# clouds_v30.net
KiCad netlist of a schematic drawn in EAGLE
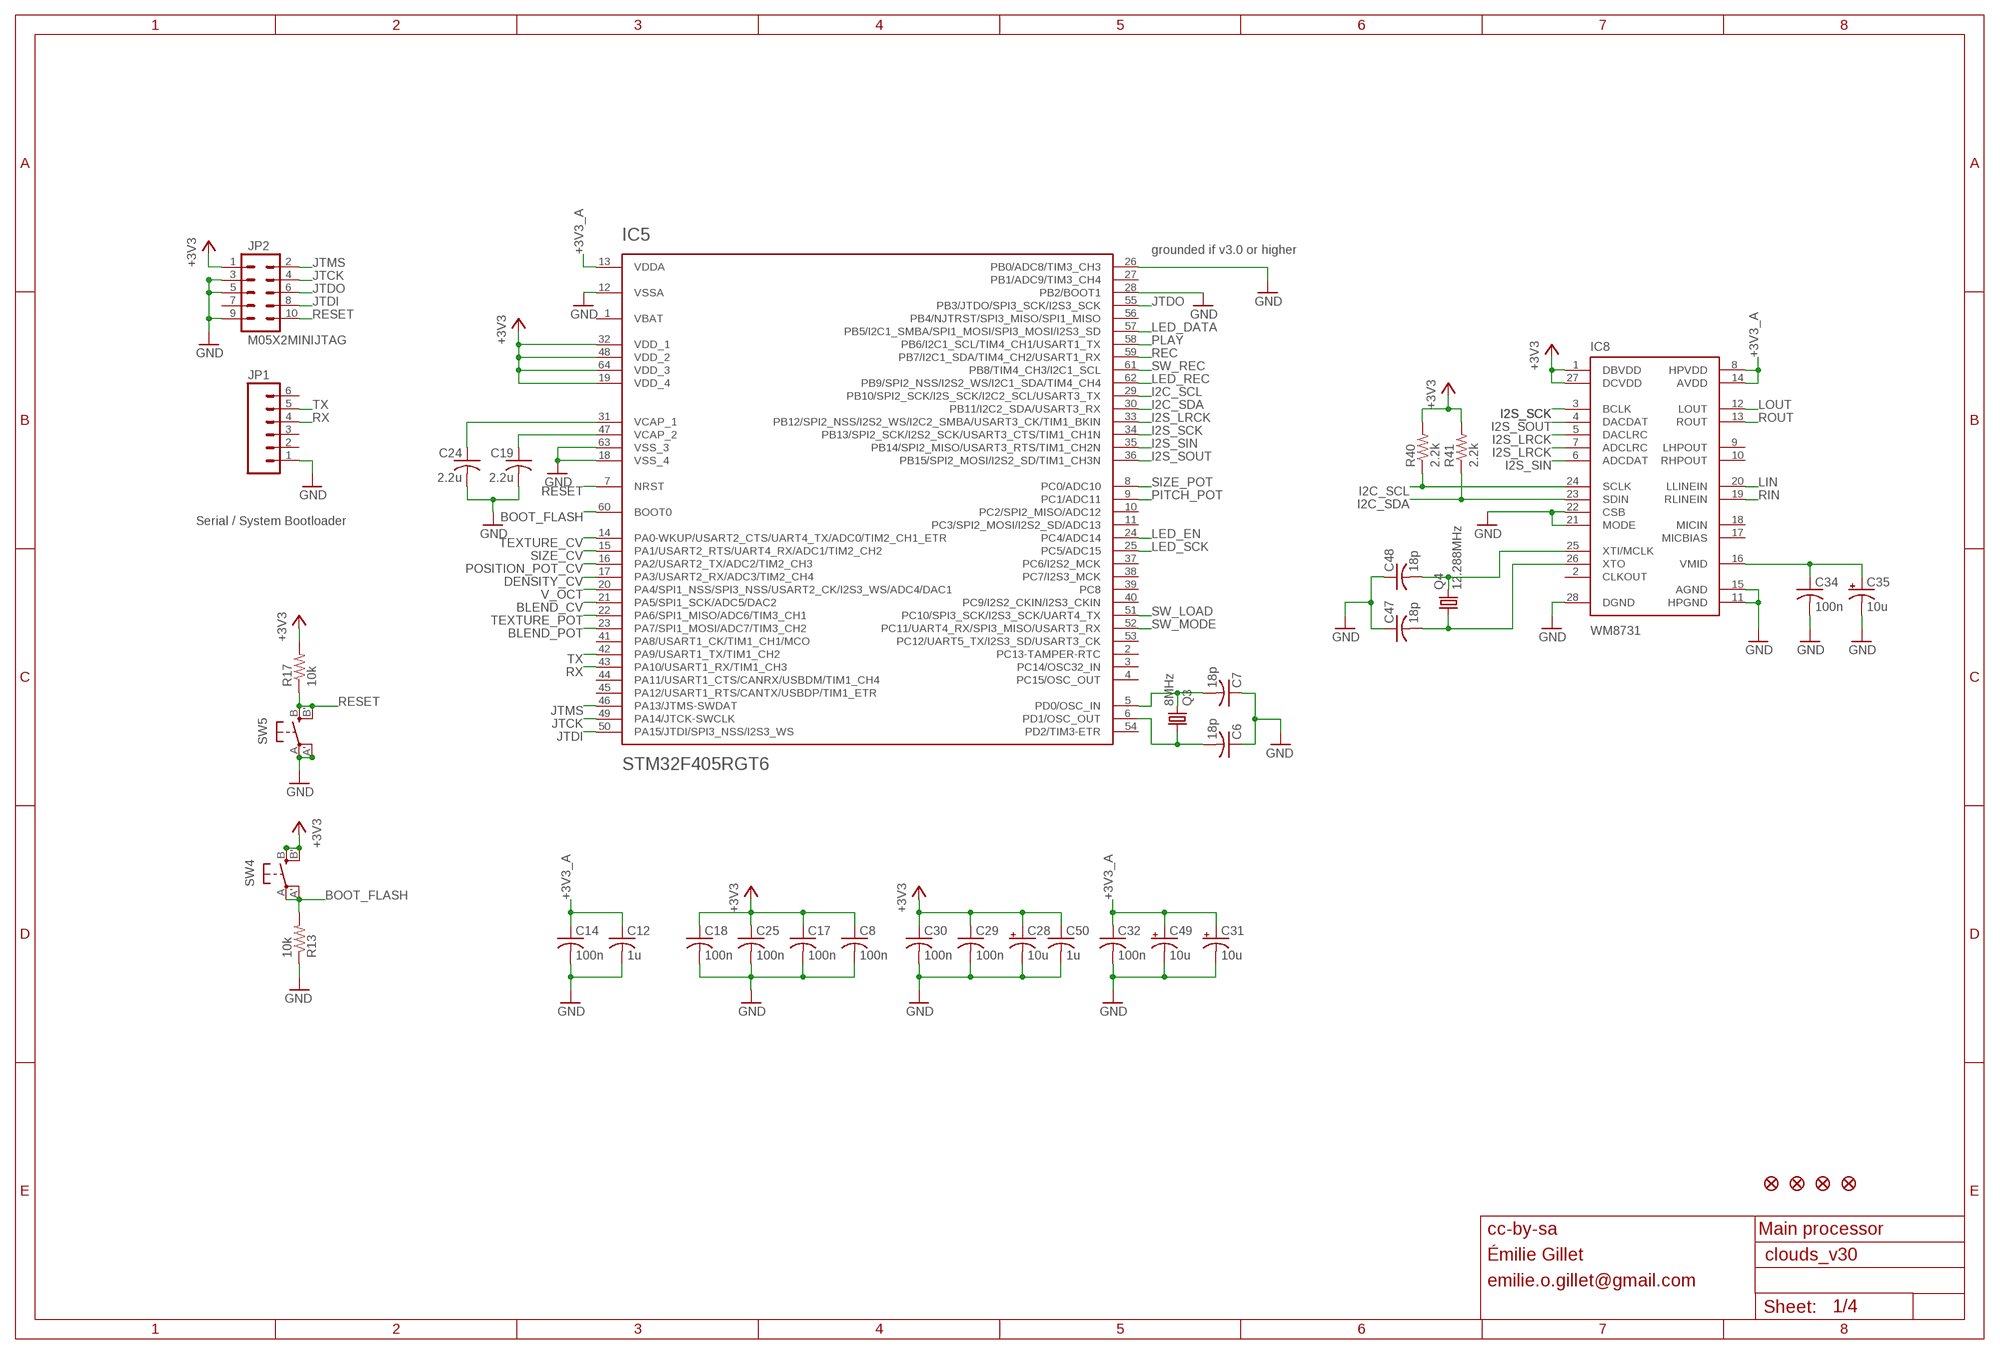
[diagram p0: schematic, sheet 1]
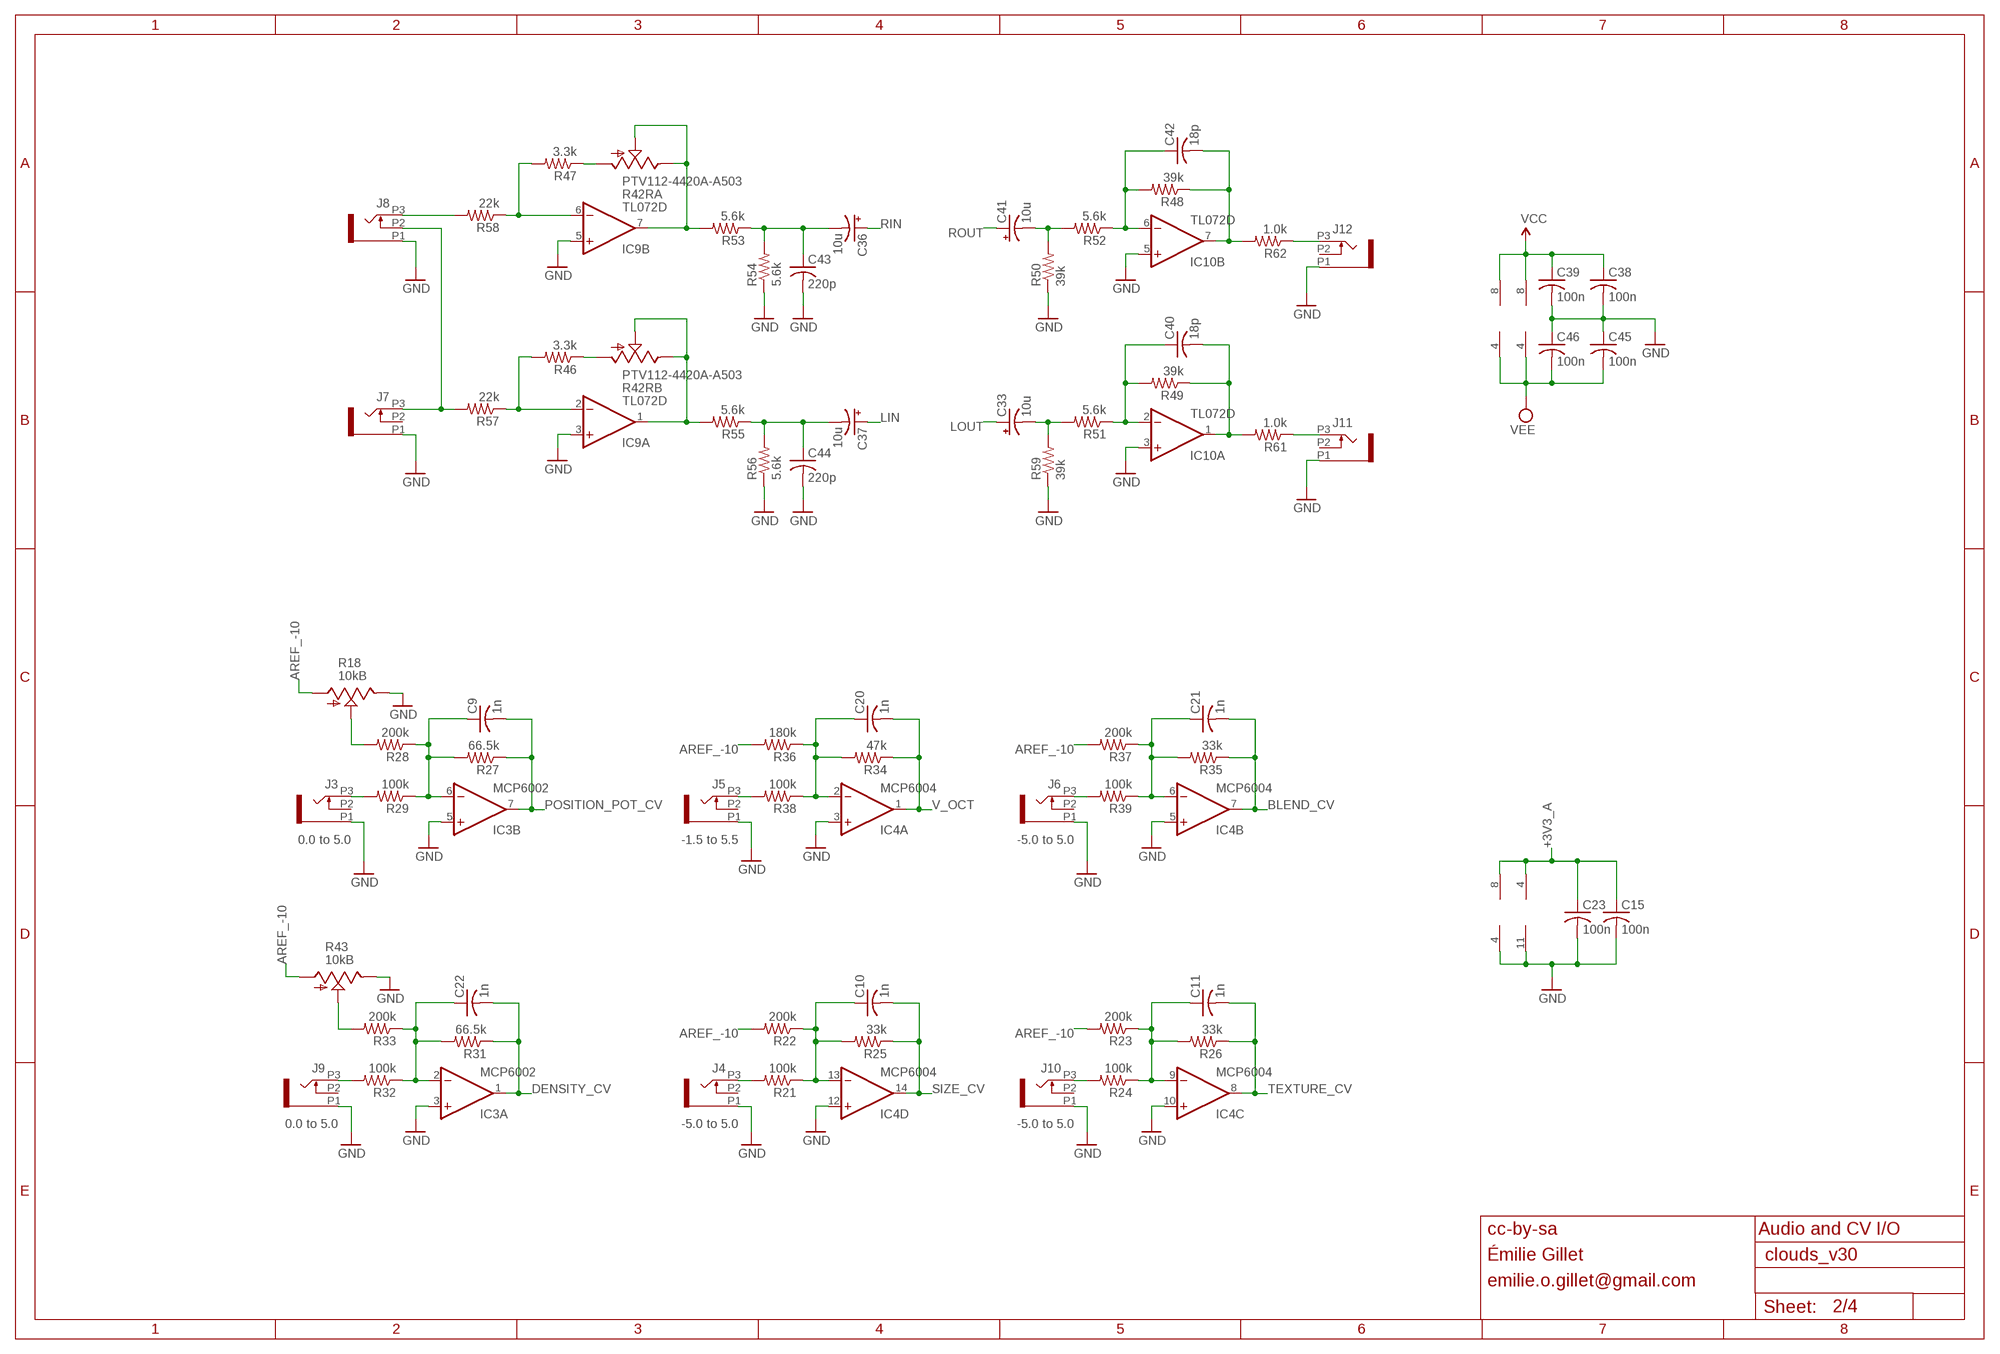
[diagram p1: schematic, sheet 2]
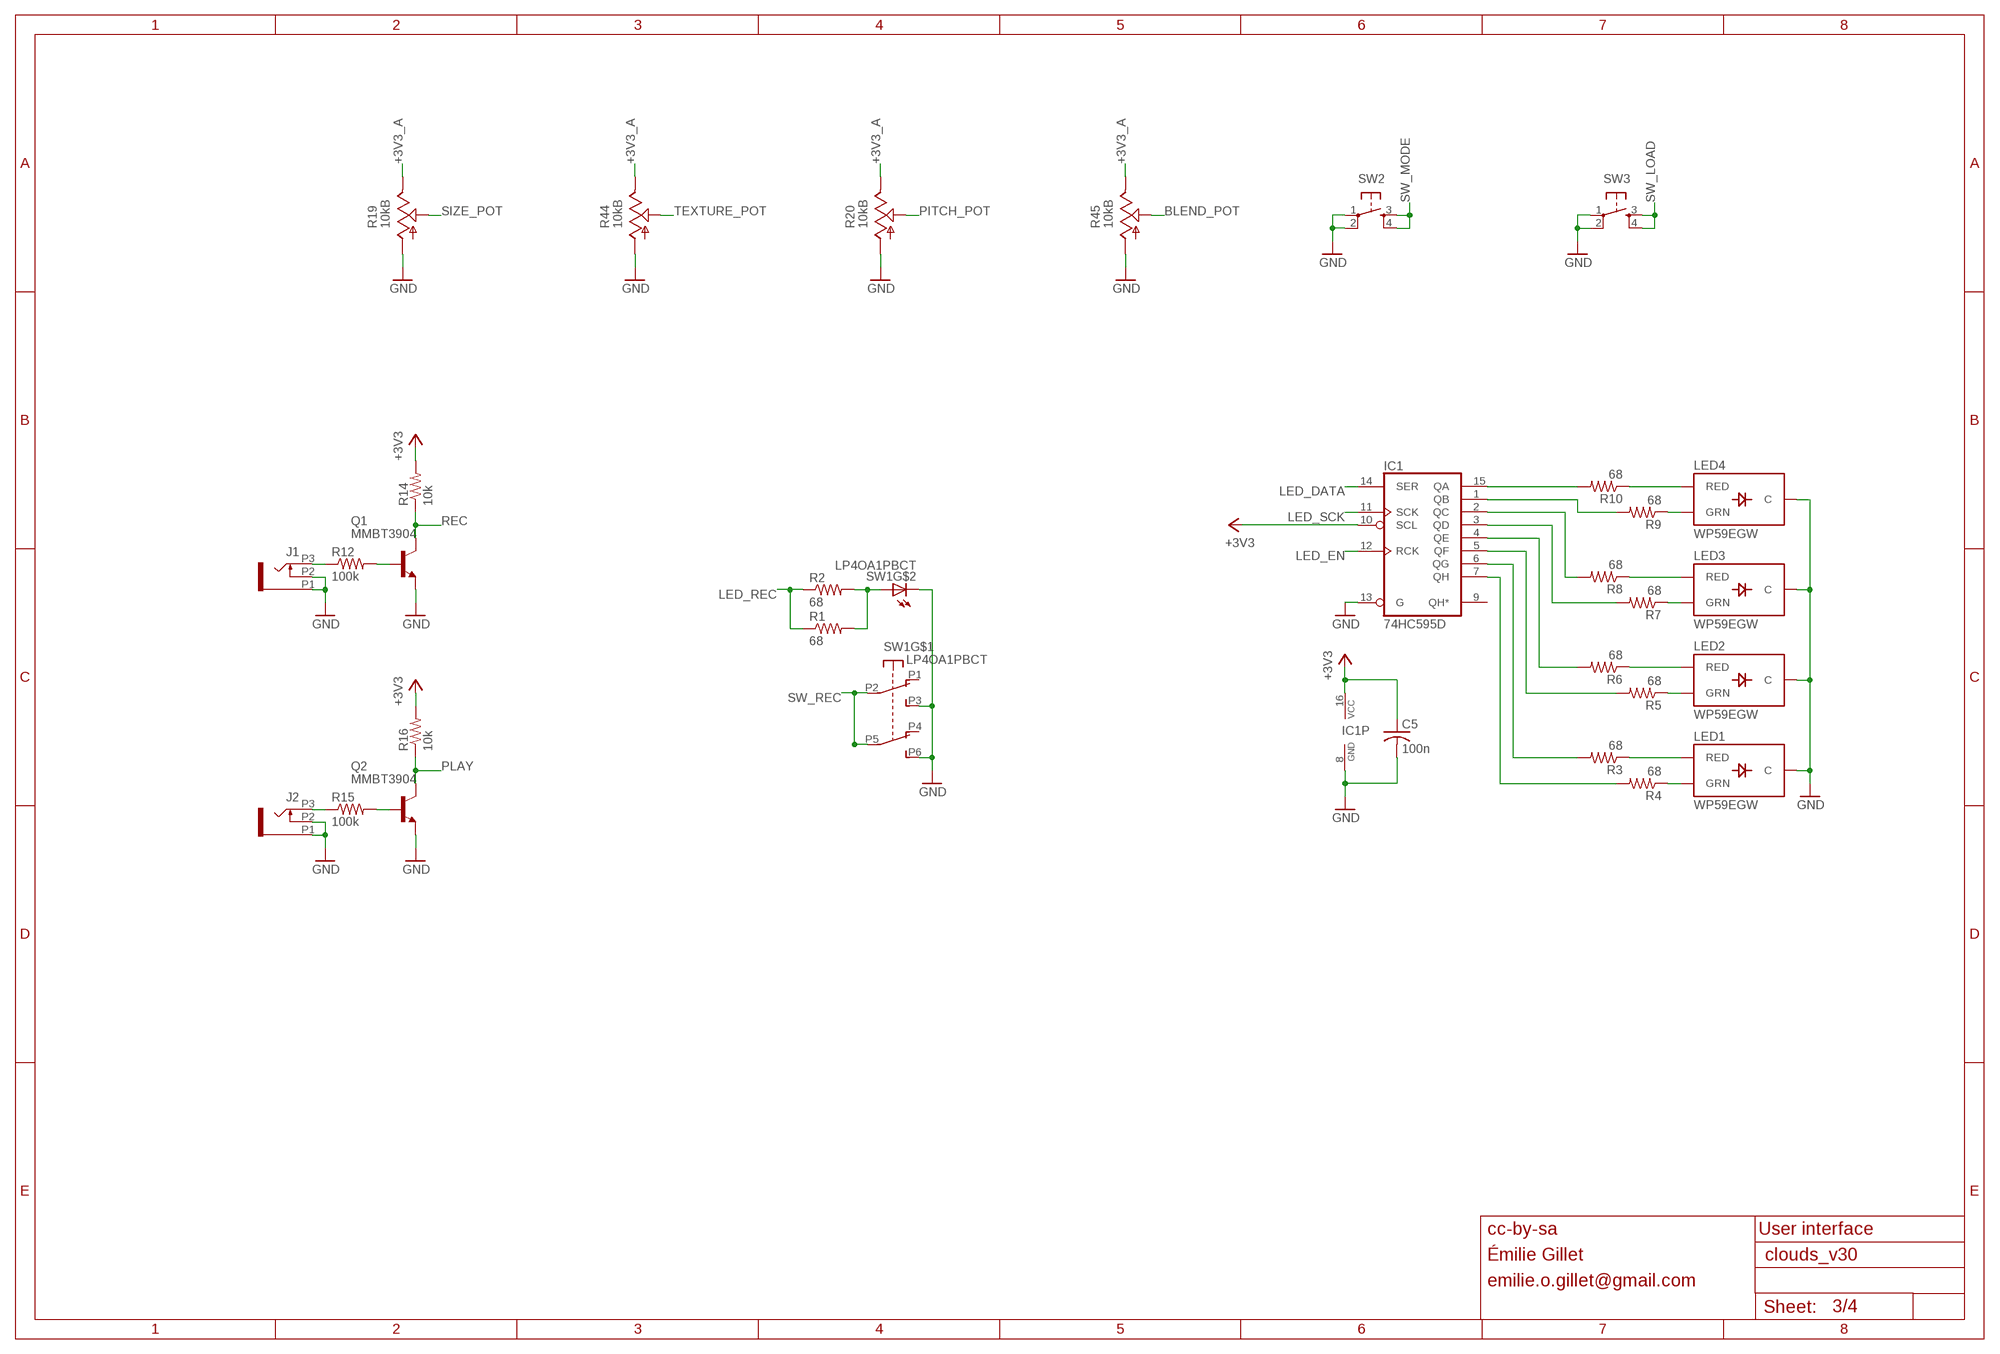
[diagram p2: schematic, sheet 3]
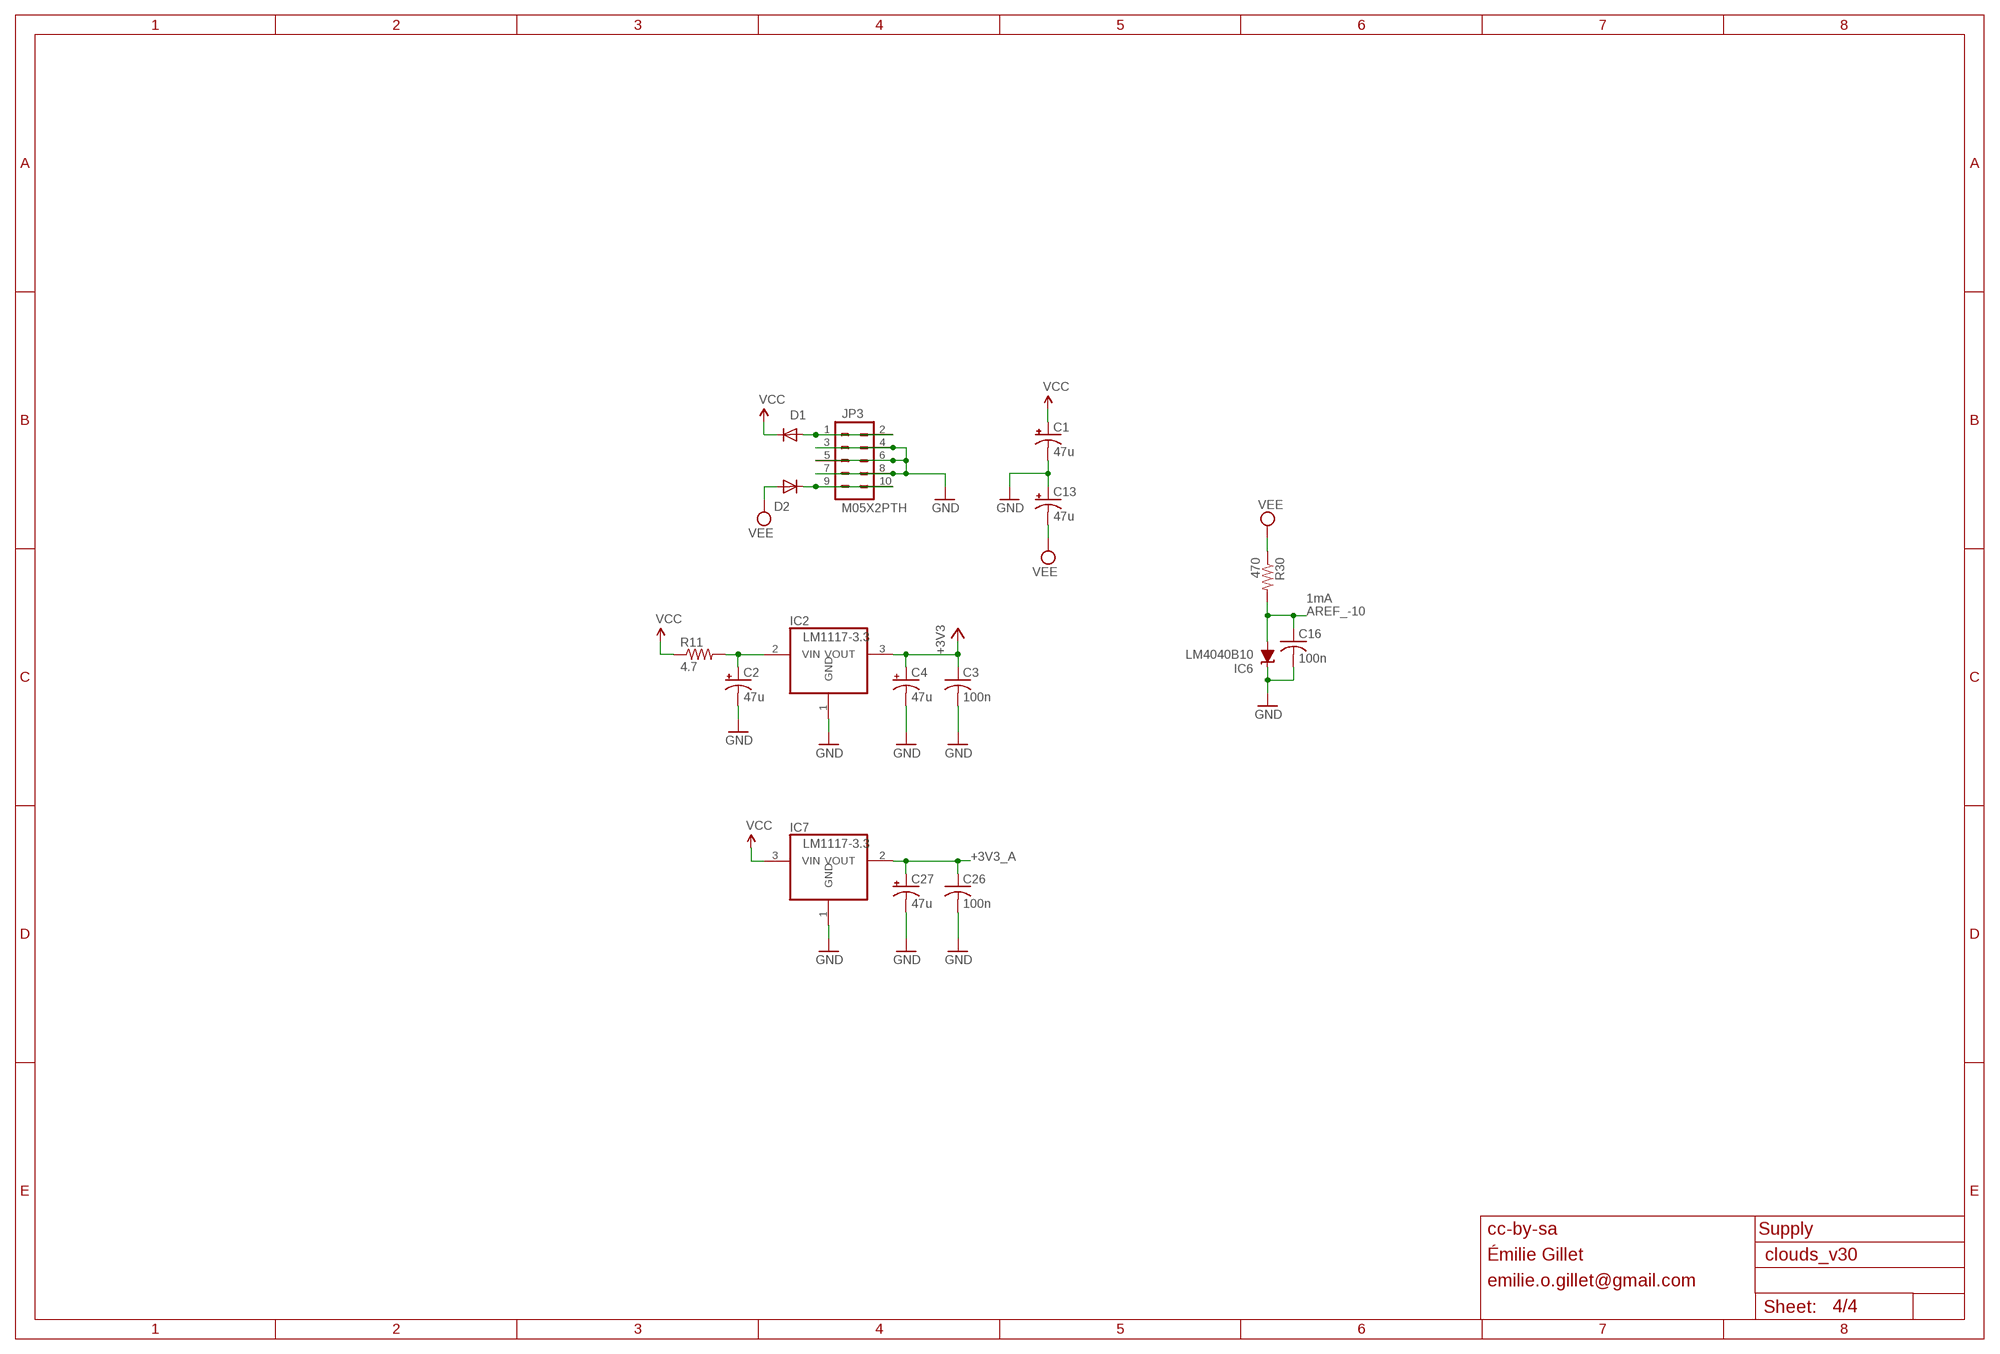
[diagram p3: schematic, sheet 4]

(export (version "E")
  (design (tool "Eeschema 10.0.6"))
  (components
    (comp (ref "C9")
      (value "1n")
      (footprint "eagle-import:C0603")
      (libsource (lib "eagle-import") (part "C-USC0603"))
    )
    (comp (ref "C10")
      (value "1n")
      (footprint "eagle-import:C0603")
      (libsource (lib "eagle-import") (part "C-USC0603"))
    )
    (comp (ref "C11")
      (value "1n")
      (footprint "eagle-import:C0603")
      (libsource (lib "eagle-import") (part "C-USC0603"))
    )
    (comp (ref "C15")
      (value "100n")
      (footprint "eagle-import:C0603")
      (libsource (lib "eagle-import") (part "C-USC0603"))
    )
    (comp (ref "C20")
      (value "1n")
      (footprint "eagle-import:C0603")
      (libsource (lib "eagle-import") (part "C-USC0603"))
    )
    (comp (ref "C21")
      (value "1n")
      (footprint "eagle-import:C0603")
      (libsource (lib "eagle-import") (part "C-USC0603"))
    )
    (comp (ref "C22")
      (value "1n")
      (footprint "eagle-import:C0603")
      (libsource (lib "eagle-import") (part "C-USC0603"))
    )
    (comp (ref "C23")
      (value "100n")
      (footprint "eagle-import:C0603")
      (libsource (lib "eagle-import") (part "C-USC0603"))
    )
    (comp (ref "C33")
      (value "10u")
      (footprint "eagle-import:PANASONIC_B")
      (libsource (lib "eagle-import") (part "CPOL-USB"))
    )
    (comp (ref "C36")
      (value "10u")
      (footprint "eagle-import:PANASONIC_B")
      (libsource (lib "eagle-import") (part "CPOL-USB"))
    )
    (comp (ref "C37")
      (value "10u")
      (footprint "eagle-import:PANASONIC_B")
      (libsource (lib "eagle-import") (part "CPOL-USB"))
    )
    (comp (ref "C38")
      (value "100n")
      (footprint "eagle-import:C0603")
      (libsource (lib "eagle-import") (part "C-USC0603"))
    )
    (comp (ref "C39")
      (value "100n")
      (footprint "eagle-import:C0603")
      (libsource (lib "eagle-import") (part "C-USC0603"))
    )
    (comp (ref "C40")
      (value "18p")
      (footprint "eagle-import:C0603")
      (libsource (lib "eagle-import") (part "C-USC0603"))
    )
    (comp (ref "C41")
      (value "10u")
      (footprint "eagle-import:PANASONIC_B")
      (libsource (lib "eagle-import") (part "CPOL-USB"))
    )
    (comp (ref "C42")
      (value "18p")
      (footprint "eagle-import:C0603")
      (libsource (lib "eagle-import") (part "C-USC0603"))
    )
    (comp (ref "C43")
      (value "220p")
      (footprint "eagle-import:C0603")
      (libsource (lib "eagle-import") (part "C-USC0603"))
    )
    (comp (ref "C44")
      (value "220p")
      (footprint "eagle-import:C0603")
      (libsource (lib "eagle-import") (part "C-USC0603"))
    )
    (comp (ref "C45")
      (value "100n")
      (footprint "eagle-import:C0603")
      (libsource (lib "eagle-import") (part "C-USC0603"))
    )
    (comp (ref "C46")
      (value "100n")
      (footprint "eagle-import:C0603")
      (libsource (lib "eagle-import") (part "C-USC0603"))
    )
    (comp (ref "IC3")
      (value "MCP6002")
      (footprint "eagle-import:SO08")
      (libsource (lib "eagle-import") (part "TL072D"))
    )
    (comp (ref "IC4")
      (value "MCP6004")
      (footprint "eagle-import:SO14")
      (libsource (lib "eagle-import") (part "TL074D"))
    )
    (comp (ref "IC9")
      (value "TL072D")
      (footprint "eagle-import:SO08")
      (libsource (lib "eagle-import") (part "og-linear_TL072D"))
    )
    (comp (ref "IC10")
      (value "TL072D")
      (footprint "eagle-import:SO08")
      (libsource (lib "eagle-import") (part "og-linear_TL072D"))
    )
    (comp (ref "J3")
      (value "PJ301_THONKICONN6")
      (footprint "eagle-import:WQP_PJ_301M6")
      (libsource (lib "eagle-import") (part "PJ301_THONKICONN6"))
    )
    (comp (ref "J4")
      (value "PJ301_THONKICONN6")
      (footprint "eagle-import:WQP_PJ_301M6")
      (libsource (lib "eagle-import") (part "PJ301_THONKICONN6"))
    )
    (comp (ref "J5")
      (value "PJ301_THONKICONN6")
      (footprint "eagle-import:WQP_PJ_301M6")
      (libsource (lib "eagle-import") (part "PJ301_THONKICONN6"))
    )
    (comp (ref "J6")
      (value "PJ301_THONKICONN6")
      (footprint "eagle-import:WQP_PJ_301M6")
      (libsource (lib "eagle-import") (part "PJ301_THONKICONN6"))
    )
    (comp (ref "J7")
      (value "PJ301_THONKICONN6")
      (footprint "eagle-import:WQP_PJ_301M6")
      (libsource (lib "eagle-import") (part "PJ301_THONKICONN6"))
    )
    (comp (ref "J8")
      (value "PJ301_THONKICONN6")
      (footprint "eagle-import:WQP_PJ_301M6")
      (libsource (lib "eagle-import") (part "PJ301_THONKICONN6"))
    )
    (comp (ref "J9")
      (value "PJ301_THONKICONN6")
      (footprint "eagle-import:WQP_PJ_301M6")
      (libsource (lib "eagle-import") (part "PJ301_THONKICONN6"))
    )
    (comp (ref "J10")
      (value "PJ301_THONKICONN6")
      (footprint "eagle-import:WQP_PJ_301M6")
      (libsource (lib "eagle-import") (part "PJ301_THONKICONN6"))
    )
    (comp (ref "J11")
      (value "PJ301_THONKICONN6")
      (footprint "eagle-import:WQP_PJ_301M6")
      (libsource (lib "eagle-import") (part "PJ301_THONKICONN6"))
    )
    (comp (ref "J12")
      (value "PJ301_THONKICONN6")
      (footprint "eagle-import:WQP_PJ_301M6")
      (libsource (lib "eagle-import") (part "PJ301_THONKICONN6"))
    )
    (comp (ref "R18")
      (value "10kB")
      (footprint "eagle-import:ALPS_POT_VERTICAL_PS")
      (libsource (lib "eagle-import") (part "POT_USVERTICAL_PS"))
    )
    (comp (ref "R21")
      (value "100k")
      (footprint "eagle-import:R0603")
      (libsource (lib "eagle-import") (part "R-US_R0603"))
    )
    (comp (ref "R22")
      (value "200k")
      (footprint "eagle-import:R0603")
      (libsource (lib "eagle-import") (part "R-US_R0603"))
    )
    (comp (ref "R23")
      (value "200k")
      (footprint "eagle-import:R0603")
      (libsource (lib "eagle-import") (part "R-US_R0603"))
    )
    (comp (ref "R24")
      (value "100k")
      (footprint "eagle-import:R0603")
      (libsource (lib "eagle-import") (part "R-US_R0603"))
    )
    (comp (ref "R25")
      (value "33k")
      (footprint "eagle-import:R0603")
      (libsource (lib "eagle-import") (part "R-US_R0603"))
    )
    (comp (ref "R26")
      (value "33k")
      (footprint "eagle-import:R0603")
      (libsource (lib "eagle-import") (part "R-US_R0603"))
    )
    (comp (ref "R27")
      (value "66.5k")
      (footprint "eagle-import:R0603")
      (libsource (lib "eagle-import") (part "R-US_R0603"))
    )
    (comp (ref "R28")
      (value "200k")
      (footprint "eagle-import:R0603")
      (libsource (lib "eagle-import") (part "R-US_R0603"))
    )
    (comp (ref "R29")
      (value "100k")
      (footprint "eagle-import:R0603")
      (libsource (lib "eagle-import") (part "R-US_R0603"))
    )
    (comp (ref "R31")
      (value "66.5k")
      (footprint "eagle-import:R0603")
      (libsource (lib "eagle-import") (part "R-US_R0603"))
    )
    (comp (ref "R32")
      (value "100k")
      (footprint "eagle-import:R0603")
      (libsource (lib "eagle-import") (part "R-US_R0603"))
    )
    (comp (ref "R33")
      (value "200k")
      (footprint "eagle-import:R0603")
      (libsource (lib "eagle-import") (part "R-US_R0603"))
    )
    (comp (ref "R34")
      (value "47k")
      (footprint "eagle-import:R0603")
      (libsource (lib "eagle-import") (part "R-US_R0603"))
    )
    (comp (ref "R35")
      (value "33k")
      (footprint "eagle-import:R0603")
      (libsource (lib "eagle-import") (part "R-US_R0603"))
    )
    (comp (ref "R36")
      (value "180k")
      (footprint "eagle-import:R0603")
      (libsource (lib "eagle-import") (part "R-US_R0603"))
    )
    (comp (ref "R37")
      (value "200k")
      (footprint "eagle-import:R0603")
      (libsource (lib "eagle-import") (part "R-US_R0603"))
    )
    (comp (ref "R38")
      (value "100k")
      (footprint "eagle-import:R0603")
      (libsource (lib "eagle-import") (part "R-US_R0603"))
    )
    (comp (ref "R39")
      (value "100k")
      (footprint "eagle-import:R0603")
      (libsource (lib "eagle-import") (part "R-US_R0603"))
    )
    (comp (ref "R42")
      (value "PTV112-4420A-A503")
      (footprint "eagle-import:BOURNS_PTV112")
      (libsource (lib "eagle-import") (part "POT_US_DUAL_GANG"))
    )
    (comp (ref "R43")
      (value "10kB")
      (footprint "eagle-import:ALPS_POT_VERTICAL_PS")
      (libsource (lib "eagle-import") (part "POT_USVERTICAL_PS"))
    )
    (comp (ref "R46")
      (value "3.3k")
      (footprint "eagle-import:R0603")
      (libsource (lib "eagle-import") (part "R-US_R0603"))
    )
    (comp (ref "R47")
      (value "3.3k")
      (footprint "eagle-import:R0603")
      (libsource (lib "eagle-import") (part "R-US_R0603"))
    )
    (comp (ref "R48")
      (value "39k")
      (footprint "eagle-import:R0603")
      (libsource (lib "eagle-import") (part "R-US_R0603"))
    )
    (comp (ref "R49")
      (value "39k")
      (footprint "eagle-import:R0603")
      (libsource (lib "eagle-import") (part "R-US_R0603"))
    )
    (comp (ref "R50")
      (value "39k")
      (footprint "eagle-import:R0603")
      (libsource (lib "eagle-import") (part "R-US_R0603"))
    )
    (comp (ref "R51")
      (value "5.6k")
      (footprint "eagle-import:R0603")
      (libsource (lib "eagle-import") (part "R-US_R0603"))
    )
    (comp (ref "R52")
      (value "5.6k")
      (footprint "eagle-import:R0603")
      (libsource (lib "eagle-import") (part "R-US_R0603"))
    )
    (comp (ref "R53")
      (value "5.6k")
      (footprint "eagle-import:R0603")
      (libsource (lib "eagle-import") (part "R-US_R0603"))
    )
    (comp (ref "R54")
      (value "5.6k")
      (footprint "eagle-import:R0603")
      (libsource (lib "eagle-import") (part "R-US_R0603"))
    )
    (comp (ref "R55")
      (value "5.6k")
      (footprint "eagle-import:R0603")
      (libsource (lib "eagle-import") (part "R-US_R0603"))
    )
    (comp (ref "R56")
      (value "5.6k")
      (footprint "eagle-import:R0603")
      (libsource (lib "eagle-import") (part "R-US_R0603"))
    )
    (comp (ref "R57")
      (value "22k")
      (footprint "eagle-import:R0603")
      (libsource (lib "eagle-import") (part "R-US_R0603"))
    )
    (comp (ref "R58")
      (value "22k")
      (footprint "eagle-import:R0603")
      (libsource (lib "eagle-import") (part "R-US_R0603"))
    )
    (comp (ref "R59")
      (value "39k")
      (footprint "eagle-import:R0603")
      (libsource (lib "eagle-import") (part "R-US_R0603"))
    )
    (comp (ref "R61")
      (value "1.0k")
      (footprint "eagle-import:R0603")
      (libsource (lib "eagle-import") (part "R-US_R0603"))
    )
    (comp (ref "R62")
      (value "1.0k")
      (footprint "eagle-import:R0603")
      (libsource (lib "eagle-import") (part "R-US_R0603"))
    )
    (comp (ref "C5")
      (value "100n")
      (footprint "eagle-import:C0603")
      (libsource (lib "eagle-import") (part "C-USC0603"))
    )
    (comp (ref "IC1")
      (value "74HC595D")
      (footprint "eagle-import:SO16")
      (libsource (lib "eagle-import") (part "74595DHC"))
    )
    (comp (ref "J1")
      (value "PJ301_THONKICONN6")
      (footprint "eagle-import:WQP_PJ_301M6")
      (libsource (lib "eagle-import") (part "PJ301_THONKICONN6"))
    )
    (comp (ref "J2")
      (value "PJ301_THONKICONN6")
      (footprint "eagle-import:WQP_PJ_301M6")
      (libsource (lib "eagle-import") (part "PJ301_THONKICONN6"))
    )
    (comp (ref "LED1")
      (value "WP59EGW")
      (footprint "eagle-import:LED-BICOLOR-THROUGHHOLE-5MM")
      (libsource (lib "eagle-import") (part "LED-BICOLOR-THROUGHHOLE5MM"))
    )
    (comp (ref "LED2")
      (value "WP59EGW")
      (footprint "eagle-import:LED-BICOLOR-THROUGHHOLE-5MM")
      (libsource (lib "eagle-import") (part "LED-BICOLOR-THROUGHHOLE5MM"))
    )
    (comp (ref "LED3")
      (value "WP59EGW")
      (footprint "eagle-import:LED-BICOLOR-THROUGHHOLE-5MM")
      (libsource (lib "eagle-import") (part "LED-BICOLOR-THROUGHHOLE5MM"))
    )
    (comp (ref "LED4")
      (value "WP59EGW")
      (footprint "eagle-import:LED-BICOLOR-THROUGHHOLE-5MM")
      (libsource (lib "eagle-import") (part "LED-BICOLOR-THROUGHHOLE5MM"))
    )
    (comp (ref "Q1")
      (value "MMBT3904")
      (footprint "eagle-import:SOT23-BEC")
      (libsource (lib "eagle-import") (part "-NPN-SOT23-BECMMBT3904LT1"))
    )
    (comp (ref "Q2")
      (value "MMBT3904")
      (footprint "eagle-import:SOT23-BEC")
      (libsource (lib "eagle-import") (part "-NPN-SOT23-BECMMBT3904LT1"))
    )
    (comp (ref "R1")
      (value "68")
      (footprint "eagle-import:R0603")
      (libsource (lib "eagle-import") (part "R-US_R0603"))
    )
    (comp (ref "R2")
      (value "68")
      (footprint "eagle-import:R0603")
      (libsource (lib "eagle-import") (part "R-US_R0603"))
    )
    (comp (ref "R3")
      (value "68")
      (footprint "eagle-import:R0603")
      (libsource (lib "eagle-import") (part "R-US_R0603"))
    )
    (comp (ref "R4")
      (value "68")
      (footprint "eagle-import:R0603")
      (libsource (lib "eagle-import") (part "R-US_R0603"))
    )
    (comp (ref "R5")
      (value "68")
      (footprint "eagle-import:R0603")
      (libsource (lib "eagle-import") (part "R-US_R0603"))
    )
    (comp (ref "R6")
      (value "68")
      (footprint "eagle-import:R0603")
      (libsource (lib "eagle-import") (part "R-US_R0603"))
    )
    (comp (ref "R7")
      (value "68")
      (footprint "eagle-import:R0603")
      (libsource (lib "eagle-import") (part "R-US_R0603"))
    )
    (comp (ref "R8")
      (value "68")
      (footprint "eagle-import:R0603")
      (libsource (lib "eagle-import") (part "R-US_R0603"))
    )
    (comp (ref "R9")
      (value "68")
      (footprint "eagle-import:R0603")
      (libsource (lib "eagle-import") (part "R-US_R0603"))
    )
    (comp (ref "R10")
      (value "68")
      (footprint "eagle-import:R0603")
      (libsource (lib "eagle-import") (part "R-US_R0603"))
    )
    (comp (ref "R12")
      (value "100k")
      (footprint "eagle-import:R0603")
      (libsource (lib "eagle-import") (part "R-US_R0603"))
    )
    (comp (ref "R14")
      (value "10k")
      (footprint "eagle-import:R0603")
      (libsource (lib "eagle-import") (part "R-US_R0603"))
    )
    (comp (ref "R15")
      (value "100k")
      (footprint "eagle-import:R0603")
      (libsource (lib "eagle-import") (part "R-US_R0603"))
    )
    (comp (ref "R16")
      (value "10k")
      (footprint "eagle-import:R0603")
      (libsource (lib "eagle-import") (part "R-US_R0603"))
    )
    (comp (ref "R19")
      (value "10kB")
      (footprint "eagle-import:ALPS_POT_VERTICAL_PS")
      (libsource (lib "eagle-import") (part "POT_USVERTICAL_PS"))
    )
    (comp (ref "R20")
      (value "10kB")
      (footprint "eagle-import:ALPS_POT_VERTICAL_PS")
      (libsource (lib "eagle-import") (part "POT_USVERTICAL_PS"))
    )
    (comp (ref "R44")
      (value "10kB")
      (footprint "eagle-import:ALPS_POT_VERTICAL_PS")
      (libsource (lib "eagle-import") (part "POT_USVERTICAL_PS"))
    )
    (comp (ref "R45")
      (value "10kB")
      (footprint "eagle-import:ALPS_POT_VERTICAL_PS")
      (libsource (lib "eagle-import") (part "POT_USVERTICAL_PS"))
    )
    (comp (ref "SW1")
      (value "LP4OA1PBCT")
      (footprint "eagle-import:LP4OA1PBCT")
      (libsource (lib "eagle-import") (part "LP4OA1PBCT"))
    )
    (comp (ref "SW2")
      (value "TAC_SWITCHPTH")
      (footprint "eagle-import:TACTILE-PTH")
      (libsource (lib "eagle-import") (part "TAC_SWITCHPTH"))
    )
    (comp (ref "SW3")
      (value "TAC_SWITCHPTH")
      (footprint "eagle-import:TACTILE-PTH")
      (libsource (lib "eagle-import") (part "TAC_SWITCHPTH"))
    )
    (comp (ref "C1")
      (value "47u")
      (footprint "eagle-import:PANASONIC_D")
      (libsource (lib "eagle-import") (part "CPOL-USD"))
    )
    (comp (ref "C2")
      (value "47u")
      (footprint "eagle-import:PANASONIC_D")
      (libsource (lib "eagle-import") (part "CPOL-USD"))
    )
    (comp (ref "C3")
      (value "100n")
      (footprint "eagle-import:C0603")
      (libsource (lib "eagle-import") (part "C-USC0603"))
    )
    (comp (ref "C4")
      (value "47u")
      (footprint "eagle-import:PANASONIC_D")
      (libsource (lib "eagle-import") (part "CPOL-USD"))
    )
    (comp (ref "C13")
      (value "47u")
      (footprint "eagle-import:PANASONIC_D")
      (libsource (lib "eagle-import") (part "CPOL-USD"))
    )
    (comp (ref "C16")
      (value "100n")
      (footprint "eagle-import:C0603")
      (libsource (lib "eagle-import") (part "C-USC0603"))
    )
    (comp (ref "C26")
      (value "100n")
      (footprint "eagle-import:C0603")
      (libsource (lib "eagle-import") (part "C-USC0603"))
    )
    (comp (ref "C27")
      (value "47u")
      (footprint "eagle-import:PANASONIC_D")
      (libsource (lib "eagle-import") (part "CPOL-USD"))
    )
    (comp (ref "D1")
      (value "1N5819HW")
      (footprint "eagle-import:SOD123")
      (libsource (lib "eagle-import") (part "DIODE-SOD123"))
    )
    (comp (ref "D2")
      (value "1N5819HW")
      (footprint "eagle-import:SOD123")
      (libsource (lib "eagle-import") (part "DIODE-SOD123"))
    )
    (comp (ref "IC2")
      (value "LM1117-3.3")
      (footprint "eagle-import:TO252")
      (libsource (lib "eagle-import") (part "REG1117T"))
    )
    (comp (ref "IC6")
      (value "LM4040B10")
      (footprint "eagle-import:DBZ_R-PDSO-G3")
      (libsource (lib "eagle-import") (part "LM4041DBZB12"))
    )
    (comp (ref "IC7")
      (value "LM1117-3.3")
      (footprint "eagle-import:SOT223")
      (libsource (lib "eagle-import") (part "REG1117"))
    )
    (comp (ref "JP3")
      (value "M05X2PTH")
      (footprint "eagle-import:AVR_ICSP")
      (libsource (lib "eagle-import") (part "M05X2PTH"))
    )
    (comp (ref "R11")
      (value "4.7")
      (footprint "eagle-import:R1206")
      (libsource (lib "eagle-import") (part "R-US_R1206"))
    )
    (comp (ref "R30")
      (value "470")
      (footprint "eagle-import:R0603")
      (libsource (lib "eagle-import") (part "R-US_R0603"))
    )
    (comp (ref "C6")
      (value "18p")
      (footprint "eagle-import:C0603")
      (libsource (lib "eagle-import") (part "C-USC0603"))
    )
    (comp (ref "C7")
      (value "18p")
      (footprint "eagle-import:C0603")
      (libsource (lib "eagle-import") (part "C-USC0603"))
    )
    (comp (ref "C8")
      (value "100n")
      (footprint "eagle-import:C0603")
      (libsource (lib "eagle-import") (part "C-USC0603"))
    )
    (comp (ref "C12")
      (value "1u")
      (footprint "eagle-import:C0603")
      (libsource (lib "eagle-import") (part "C-USC0603"))
    )
    (comp (ref "C14")
      (value "100n")
      (footprint "eagle-import:C0603")
      (libsource (lib "eagle-import") (part "C-USC0603"))
    )
    (comp (ref "C17")
      (value "100n")
      (footprint "eagle-import:C0603")
      (libsource (lib "eagle-import") (part "C-USC0603"))
    )
    (comp (ref "C18")
      (value "100n")
      (footprint "eagle-import:C0603")
      (libsource (lib "eagle-import") (part "C-USC0603"))
    )
    (comp (ref "C19")
      (value "2.2u")
      (footprint "eagle-import:C0805")
      (libsource (lib "eagle-import") (part "C-USC0805"))
    )
    (comp (ref "C24")
      (value "2.2u")
      (footprint "eagle-import:C0805")
      (libsource (lib "eagle-import") (part "C-USC0805"))
    )
    (comp (ref "C25")
      (value "100n")
      (footprint "eagle-import:C0603")
      (libsource (lib "eagle-import") (part "C-USC0603"))
    )
    (comp (ref "C28")
      (value "10u")
      (footprint "eagle-import:PANASONIC_A")
      (libsource (lib "eagle-import") (part "CPOL-USA"))
    )
    (comp (ref "C29")
      (value "100n")
      (footprint "eagle-import:C0603")
      (libsource (lib "eagle-import") (part "C-USC0603"))
    )
    (comp (ref "C30")
      (value "100n")
      (footprint "eagle-import:C0603")
      (libsource (lib "eagle-import") (part "C-USC0603"))
    )
    (comp (ref "C31")
      (value "10u")
      (footprint "eagle-import:PANASONIC_B")
      (libsource (lib "eagle-import") (part "CPOL-USB"))
    )
    (comp (ref "C32")
      (value "100n")
      (footprint "eagle-import:C0603")
      (libsource (lib "eagle-import") (part "C-USC0603"))
    )
    (comp (ref "C34")
      (value "100n")
      (footprint "eagle-import:C0603")
      (libsource (lib "eagle-import") (part "C-USC0603"))
    )
    (comp (ref "C35")
      (value "10u")
      (footprint "eagle-import:PANASONIC_B")
      (libsource (lib "eagle-import") (part "CPOL-USB"))
    )
    (comp (ref "C47")
      (value "18p")
      (footprint "eagle-import:C0603")
      (libsource (lib "eagle-import") (part "C-USC0603"))
    )
    (comp (ref "C48")
      (value "18p")
      (footprint "eagle-import:C0603")
      (libsource (lib "eagle-import") (part "C-USC0603"))
    )
    (comp (ref "C49")
      (value "10u")
      (footprint "eagle-import:PANASONIC_A")
      (libsource (lib "eagle-import") (part "CPOL-USA"))
    )
    (comp (ref "C50")
      (value "1u")
      (footprint "eagle-import:C0603")
      (libsource (lib "eagle-import") (part "C-USC0603"))
    )
    (comp (ref "F1")
      (value "FIDUCIAL1X2")
      (footprint "eagle-import:FIDUCIAL-1X2")
      (libsource (lib "eagle-import") (part "FIDUCIAL1X2"))
    )
    (comp (ref "F2")
      (value "FIDUCIAL1X2")
      (footprint "eagle-import:FIDUCIAL-1X2")
      (libsource (lib "eagle-import") (part "FIDUCIAL1X2"))
    )
    (comp (ref "F3")
      (value "FIDUCIAL1X2")
      (footprint "eagle-import:FIDUCIAL-1X2")
      (libsource (lib "eagle-import") (part "FIDUCIAL1X2"))
    )
    (comp (ref "F4")
      (value "FIDUCIAL1X2")
      (footprint "eagle-import:FIDUCIAL-1X2")
      (libsource (lib "eagle-import") (part "FIDUCIAL1X2"))
    )
    (comp (ref "IC5")
      (value "STM32F405RGT6")
      (footprint "eagle-import:TQFP-10X10-64")
      (libsource (lib "eagle-import") (part "STM32F20X"))
    )
    (comp (ref "IC8")
      (value "WM8731")
      (footprint "eagle-import:SSOP28")
      (libsource (lib "eagle-import") (part "WM8731"))
    )
    (comp (ref "JP1")
      (value "M06SIP")
      (footprint "eagle-import:1X06")
      (libsource (lib "eagle-import") (part "M06SIP"))
    )
    (comp (ref "JP2")
      (value "M05X2MINIJTAG")
      (footprint "eagle-import:2X5-1.27")
      (libsource (lib "eagle-import") (part "M05X2MINIJTAG"))
    )
    (comp (ref "Q3")
      (value "8MHz")
      (footprint "eagle-import:HC49UP")
      (libsource (lib "eagle-import") (part "CRYSTALHC49UP"))
    )
    (comp (ref "Q4")
      (value "12.288MHz")
      (footprint "eagle-import:HC49UP")
      (libsource (lib "eagle-import") (part "CRYSTALHC49UP"))
    )
    (comp (ref "R13")
      (value "10k")
      (footprint "eagle-import:R0603")
      (libsource (lib "eagle-import") (part "R-US_R0603"))
    )
    (comp (ref "R17")
      (value "10k")
      (footprint "eagle-import:R0603")
      (libsource (lib "eagle-import") (part "R-US_R0603"))
    )
    (comp (ref "R40")
      (value "2.2k")
      (footprint "eagle-import:R0603")
      (libsource (lib "eagle-import") (part "R-US_R0603"))
    )
    (comp (ref "R41")
      (value "2.2k")
      (footprint "eagle-import:R0603")
      (libsource (lib "eagle-import") (part "R-US_R0603"))
    )
    (comp (ref "SW4")
      (value "EVQQ2")
      (footprint "eagle-import:EVQ-Q2")
      (libsource (lib "eagle-import") (part "EVQQ2"))
    )
    (comp (ref "SW5")
      (value "EVQQ2")
      (footprint "eagle-import:EVQ-Q2")
      (libsource (lib "eagle-import") (part "EVQQ2"))
    )
  )
  (nets
    (net (code "1") (name "+3V3") (class "Default")
      (node (ref "C17") (pin "1") (pinfunction "1_1") (pintype "passive"))
      (node (ref "C18") (pin "1") (pinfunction "1_1") (pintype "passive"))
      (node (ref "C25") (pin "1") (pinfunction "1_1") (pintype "passive"))
      (node (ref "C28") (pin "+") (pinfunction "+_+") (pintype "passive"))
      (node (ref "C29") (pin "1") (pinfunction "1_1") (pintype "passive"))
      (node (ref "C3") (pin "1") (pinfunction "1_1") (pintype "passive"))
      (node (ref "C30") (pin "1") (pinfunction "1_1") (pintype "passive"))
      (node (ref "C4") (pin "+") (pinfunction "+_+") (pintype "passive"))
      (node (ref "C5") (pin "1") (pinfunction "1_1") (pintype "passive"))
      (node (ref "C50") (pin "1") (pinfunction "1_1") (pintype "passive"))
      (node (ref "C8") (pin "1") (pinfunction "1_1") (pintype "passive"))
      (node (ref "IC1") (pin "10") (pinfunction "SCL_10") (pintype "input"))
      (node (ref "IC1") (pin "16") (pinfunction "VCC_16") (pintype "power_in"))
      (node (ref "IC2") (pin "3") (pinfunction "VOUT_3") (pintype "output"))
      (node (ref "IC5") (pin "19") (pinfunction "VDD_4_19") (pintype "power_in"))
      (node (ref "IC5") (pin "32") (pinfunction "VDD_1_32") (pintype "power_in"))
      (node (ref "IC5") (pin "48") (pinfunction "VDD_2_48") (pintype "power_in"))
      (node (ref "IC5") (pin "64") (pinfunction "VDD_3_64") (pintype "power_in"))
      (node (ref "IC8") (pin "1") (pinfunction "DBVDD_1") (pintype "bidirectional"))
      (node (ref "IC8") (pin "27") (pinfunction "DCVDD_27") (pintype "bidirectional"))
      (node (ref "JP2") (pin "1") (pinfunction "1_1") (pintype "passive"))
      (node (ref "R14") (pin "2") (pinfunction "2_2") (pintype "passive"))
      (node (ref "R16") (pin "2") (pinfunction "2_2") (pintype "passive"))
      (node (ref "R17") (pin "2") (pinfunction "2_2") (pintype "passive"))
      (node (ref "R40") (pin "2") (pinfunction "2_2") (pintype "passive"))
      (node (ref "R41") (pin "2") (pinfunction "2_2") (pintype "passive"))
      (node (ref "SW4") (pin "B") (pinfunction "S_B") (pintype "passive"))
      (node (ref "SW4") (pin "B'") (pinfunction "S1_B'") (pintype "passive"))
    )
    (net (code "2") (name "+3V3_A") (class "Default")
      (node (ref "C12") (pin "1") (pinfunction "1_1") (pintype "passive"))
      (node (ref "C14") (pin "1") (pinfunction "1_1") (pintype "passive"))
      (node (ref "C15") (pin "1") (pinfunction "1_1") (pintype "passive"))
      (node (ref "C23") (pin "1") (pinfunction "1_1") (pintype "passive"))
      (node (ref "C26") (pin "1") (pinfunction "1_1") (pintype "passive"))
      (node (ref "C27") (pin "+") (pinfunction "+_+") (pintype "passive"))
      (node (ref "C31") (pin "+") (pinfunction "+_+") (pintype "passive"))
      (node (ref "C32") (pin "1") (pinfunction "1_1") (pintype "passive"))
      (node (ref "C49") (pin "+") (pinfunction "+_+") (pintype "passive"))
      (node (ref "IC3") (pin "8") (pinfunction "V+_8") (pintype "power_in"))
      (node (ref "IC4") (pin "4") (pinfunction "V+_4") (pintype "power_in"))
      (node (ref "IC5") (pin "13") (pinfunction "VDDA_13") (pintype "power_in"))
      (node (ref "IC7") (pin "2") (pinfunction "VOUT_2") (pintype "output"))
      (node (ref "IC8") (pin "14") (pinfunction "AVDD_14") (pintype "bidirectional"))
      (node (ref "IC8") (pin "8") (pinfunction "HPVDD_8") (pintype "bidirectional"))
      (node (ref "R19") (pin "P$1") (pinfunction "E_P$1") (pintype "passive"))
      (node (ref "R20") (pin "P$1") (pinfunction "E_P$1") (pintype "passive"))
      (node (ref "R44") (pin "P$1") (pinfunction "E_P$1") (pintype "passive"))
      (node (ref "R45") (pin "P$1") (pinfunction "E_P$1") (pintype "passive"))
    )
    (net (code "3") (name "AREF_-10") (class "Default")
      (node (ref "C16") (pin "1") (pinfunction "1_1") (pintype "passive"))
      (node (ref "IC6") (pin "2") (pinfunction "A_2") (pintype "passive"))
      (node (ref "R18") (pin "P$3") (pinfunction "A_P$3") (pintype "passive"))
      (node (ref "R22") (pin "2") (pinfunction "2_2") (pintype "passive"))
      (node (ref "R23") (pin "2") (pinfunction "2_2") (pintype "passive"))
      (node (ref "R30") (pin "2") (pinfunction "2_2") (pintype "passive"))
      (node (ref "R36") (pin "2") (pinfunction "2_2") (pintype "passive"))
      (node (ref "R37") (pin "2") (pinfunction "2_2") (pintype "passive"))
      (node (ref "R43") (pin "P$3") (pinfunction "A_P$3") (pintype "passive"))
    )
    (net (code "4") (name "BLEND_CV") (class "Default")
      (node (ref "C21") (pin "2") (pinfunction "2_2") (pintype "passive"))
      (node (ref "IC4") (pin "7") (pinfunction "OUT_7") (pintype "output"))
      (node (ref "IC5") (pin "21") (pinfunction "PA5/SPI1_SCK/ADC5/DAC2_21") (pintype "bidirectional"))
      (node (ref "R35") (pin "1") (pinfunction "1_1") (pintype "passive"))
    )
    (net (code "5") (name "BLEND_POT") (class "Default")
      (node (ref "IC5") (pin "23") (pinfunction "PA7/SPI1_MOSI/ADC7/TIM3_CH2_23") (pintype "bidirectional"))
      (node (ref "R45") (pin "P$2") (pinfunction "S_P$2") (pintype "passive"))
    )
    (net (code "6") (name "BOOT_FLASH") (class "Default")
      (node (ref "IC5") (pin "60") (pinfunction "BOOT0_60") (pintype "bidirectional"))
      (node (ref "R13") (pin "2") (pinfunction "2_2") (pintype "passive"))
      (node (ref "SW4") (pin "A") (pinfunction "P_A") (pintype "passive"))
      (node (ref "SW4") (pin "A'") (pinfunction "P1_A'") (pintype "passive"))
    )
    (net (code "7") (name "DENSITY_CV") (class "Default")
      (node (ref "C22") (pin "2") (pinfunction "2_2") (pintype "passive"))
      (node (ref "IC3") (pin "1") (pinfunction "OUT_1") (pintype "output"))
      (node (ref "IC5") (pin "17") (pinfunction "PA3/USART2_RX/ADC3/TIM2_CH4_17") (pintype "bidirectional"))
      (node (ref "R31") (pin "1") (pinfunction "1_1") (pintype "passive"))
    )
    (net (code "8") (name "GND") (class "Default")
      (node (ref "C1") (pin "-") (pinfunction "-_-") (pintype "passive"))
      (node (ref "C12") (pin "2") (pinfunction "2_2") (pintype "passive"))
      (node (ref "C13") (pin "+") (pinfunction "+_+") (pintype "passive"))
      (node (ref "C14") (pin "2") (pinfunction "2_2") (pintype "passive"))
      (node (ref "C15") (pin "2") (pinfunction "2_2") (pintype "passive"))
      (node (ref "C16") (pin "2") (pinfunction "2_2") (pintype "passive"))
      (node (ref "C17") (pin "2") (pinfunction "2_2") (pintype "passive"))
      (node (ref "C18") (pin "2") (pinfunction "2_2") (pintype "passive"))
      (node (ref "C19") (pin "2") (pinfunction "2_2") (pintype "passive"))
      (node (ref "C2") (pin "-") (pinfunction "-_-") (pintype "passive"))
      (node (ref "C23") (pin "2") (pinfunction "2_2") (pintype "passive"))
      (node (ref "C24") (pin "2") (pinfunction "2_2") (pintype "passive"))
      (node (ref "C25") (pin "2") (pinfunction "2_2") (pintype "passive"))
      (node (ref "C26") (pin "2") (pinfunction "2_2") (pintype "passive"))
      (node (ref "C27") (pin "-") (pinfunction "-_-") (pintype "passive"))
      (node (ref "C28") (pin "-") (pinfunction "-_-") (pintype "passive"))
      (node (ref "C29") (pin "2") (pinfunction "2_2") (pintype "passive"))
      (node (ref "C3") (pin "2") (pinfunction "2_2") (pintype "passive"))
      (node (ref "C30") (pin "2") (pinfunction "2_2") (pintype "passive"))
      (node (ref "C31") (pin "-") (pinfunction "-_-") (pintype "passive"))
      (node (ref "C32") (pin "2") (pinfunction "2_2") (pintype "passive"))
      (node (ref "C34") (pin "2") (pinfunction "2_2") (pintype "passive"))
      (node (ref "C35") (pin "-") (pinfunction "-_-") (pintype "passive"))
      (node (ref "C38") (pin "2") (pinfunction "2_2") (pintype "passive"))
      (node (ref "C39") (pin "2") (pinfunction "2_2") (pintype "passive"))
      (node (ref "C4") (pin "-") (pinfunction "-_-") (pintype "passive"))
      (node (ref "C43") (pin "2") (pinfunction "2_2") (pintype "passive"))
      (node (ref "C44") (pin "2") (pinfunction "2_2") (pintype "passive"))
      (node (ref "C45") (pin "1") (pinfunction "1_1") (pintype "passive"))
      (node (ref "C46") (pin "1") (pinfunction "1_1") (pintype "passive"))
      (node (ref "C47") (pin "1") (pinfunction "1_1") (pintype "passive"))
      (node (ref "C48") (pin "1") (pinfunction "1_1") (pintype "passive"))
      (node (ref "C49") (pin "-") (pinfunction "-_-") (pintype "passive"))
      (node (ref "C5") (pin "2") (pinfunction "2_2") (pintype "passive"))
      (node (ref "C50") (pin "2") (pinfunction "2_2") (pintype "passive"))
      (node (ref "C6") (pin "1") (pinfunction "1_1") (pintype "passive"))
      (node (ref "C7") (pin "1") (pinfunction "1_1") (pintype "passive"))
      (node (ref "C8") (pin "2") (pinfunction "2_2") (pintype "passive"))
      (node (ref "IC1") (pin "13") (pinfunction "G_13") (pintype "input"))
      (node (ref "IC1") (pin "8") (pinfunction "GND_8") (pintype "power_in"))
      (node (ref "IC10") (pin "3") (pinfunction "+IN_3") (pintype "input"))
      (node (ref "IC10") (pin "5") (pinfunction "+IN_5") (pintype "input"))
      (node (ref "IC2") (pin "1") (pinfunction "GND_1") (pintype "power_in"))
      (node (ref "IC3") (pin "3") (pinfunction "+IN_3") (pintype "input"))
      (node (ref "IC3") (pin "4") (pinfunction "V-_4") (pintype "power_in"))
      (node (ref "IC3") (pin "5") (pinfunction "+IN_5") (pintype "input"))
      (node (ref "IC4") (pin "10") (pinfunction "+IN_10") (pintype "input"))
      (node (ref "IC4") (pin "11") (pinfunction "V-_11") (pintype "power_in"))
      (node (ref "IC4") (pin "12") (pinfunction "+IN_12") (pintype "input"))
      (node (ref "IC4") (pin "3") (pinfunction "+IN_3") (pintype "input"))
      (node (ref "IC4") (pin "5") (pinfunction "+IN_5") (pintype "input"))
      (node (ref "IC5") (pin "12") (pinfunction "VSSA_12") (pintype "power_in"))
      (node (ref "IC5") (pin "18") (pinfunction "VSS_4_18") (pintype "power_in"))
      (node (ref "IC5") (pin "26") (pinfunction "PB0/ADC8/TIM3_CH3_26") (pintype "bidirectional"))
      (node (ref "IC5") (pin "28") (pinfunction "PB2/BOOT1_28") (pintype "bidirectional"))
      (node (ref "IC5") (pin "63") (pinfunction "VSS_3_63") (pintype "power_in"))
      (node (ref "IC6") (pin "1") (pinfunction "C_1") (pintype "passive"))
      (node (ref "IC7") (pin "1") (pinfunction "GND_1") (pintype "power_in"))
      (node (ref "IC8") (pin "11") (pinfunction "HPGND_11") (pintype "bidirectional"))
      (node (ref "IC8") (pin "15") (pinfunction "AGND_15") (pintype "bidirectional"))
      (node (ref "IC8") (pin "21") (pinfunction "MODE_21") (pintype "bidirectional"))
      (node (ref "IC8") (pin "22") (pinfunction "CSB_22") (pintype "bidirectional"))
      (node (ref "IC8") (pin "28") (pinfunction "DGND_28") (pintype "bidirectional"))
      (node (ref "IC9") (pin "3") (pinfunction "+IN_3") (pintype "input"))
      (node (ref "IC9") (pin "5") (pinfunction "+IN_5") (pintype "input"))
      (node (ref "J1") (pin "P1") (pinfunction "1_P1") (pintype "passive"))
      (node (ref "J1") (pin "P2") (pinfunction "2_P2") (pintype "passive"))
      (node (ref "J10") (pin "P1") (pinfunction "1_P1") (pintype "passive"))
      (node (ref "J11") (pin "P1") (pinfunction "1_P1") (pintype "passive"))
      (node (ref "J12") (pin "P1") (pinfunction "1_P1") (pintype "passive"))
      (node (ref "J2") (pin "P1") (pinfunction "1_P1") (pintype "passive"))
      (node (ref "J2") (pin "P2") (pinfunction "2_P2") (pintype "passive"))
      (node (ref "J3") (pin "P1") (pinfunction "1_P1") (pintype "passive"))
      (node (ref "J4") (pin "P1") (pinfunction "1_P1") (pintype "passive"))
      (node (ref "J5") (pin "P1") (pinfunction "1_P1") (pintype "passive"))
      (node (ref "J6") (pin "P1") (pinfunction "1_P1") (pintype "passive"))
      (node (ref "J7") (pin "P1") (pinfunction "1_P1") (pintype "passive"))
      (node (ref "J8") (pin "P1") (pinfunction "1_P1") (pintype "passive"))
      (node (ref "J9") (pin "P1") (pinfunction "1_P1") (pintype "passive"))
      (node (ref "JP1") (pin "1") (pinfunction "1_1") (pintype "passive"))
      (node (ref "JP2") (pin "3") (pinfunction "3_3") (pintype "passive"))
      (node (ref "JP2") (pin "5") (pinfunction "5_5") (pintype "passive"))
      (node (ref "JP2") (pin "9") (pinfunction "9_9") (pintype "passive"))
      (node (ref "JP3") (pin "3") (pinfunction "3_3") (pintype "passive"))
      (node (ref "JP3") (pin "4") (pinfunction "4_4") (pintype "passive"))
      (node (ref "JP3") (pin "5") (pinfunction "5_5") (pintype "passive"))
      (node (ref "JP3") (pin "6") (pinfunction "6_6") (pintype "passive"))
      (node (ref "JP3") (pin "7") (pinfunction "7_7") (pintype "passive"))
      (node (ref "JP3") (pin "8") (pinfunction "8_8") (pintype "passive"))
      (node (ref "LED1") (pin "2") (pinfunction "C_2") (pintype "bidirectional"))
      (node (ref "LED2") (pin "2") (pinfunction "C_2") (pintype "bidirectional"))
      (node (ref "LED3") (pin "2") (pinfunction "C_2") (pintype "bidirectional"))
      (node (ref "LED4") (pin "2") (pinfunction "C_2") (pintype "bidirectional"))
      (node (ref "Q1") (pin "E") (pinfunction "E_E") (pintype "passive"))
      (node (ref "Q2") (pin "E") (pinfunction "E_E") (pintype "passive"))
      (node (ref "R13") (pin "1") (pinfunction "1_1") (pintype "passive"))
      (node (ref "R18") (pin "P$1") (pinfunction "E_P$1") (pintype "passive"))
      (node (ref "R19") (pin "P$3") (pinfunction "A_P$3") (pintype "passive"))
      (node (ref "R20") (pin "P$3") (pinfunction "A_P$3") (pintype "passive"))
      (node (ref "R43") (pin "P$1") (pinfunction "E_P$1") (pintype "passive"))
      (node (ref "R44") (pin "P$3") (pinfunction "A_P$3") (pintype "passive"))
      (node (ref "R45") (pin "P$3") (pinfunction "A_P$3") (pintype "passive"))
      (node (ref "R50") (pin "1") (pinfunction "1_1") (pintype "passive"))
      (node (ref "R54") (pin "1") (pinfunction "1_1") (pintype "passive"))
      (node (ref "R56") (pin "1") (pinfunction "1_1") (pintype "passive"))
      (node (ref "R59") (pin "1") (pinfunction "1_1") (pintype "passive"))
      (node (ref "SW1") (pin "L2") (pinfunction "L2_L2") (pintype "passive"))
      (node (ref "SW1") (pin "P3") (pinfunction "A3_P3") (pintype "passive"))
      (node (ref "SW1") (pin "P6") (pinfunction "B3_P6") (pintype "passive"))
      (node (ref "SW2") (pin "1") (pinfunction "1_1") (pintype "passive"))
      (node (ref "SW2") (pin "2") (pinfunction "2_2") (pintype "passive"))
      (node (ref "SW3") (pin "1") (pinfunction "1_1") (pintype "passive"))
      (node (ref "SW3") (pin "2") (pinfunction "2_2") (pintype "passive"))
      (node (ref "SW5") (pin "A") (pinfunction "P_A") (pintype "passive"))
      (node (ref "SW5") (pin "A'") (pinfunction "P1_A'") (pintype "passive"))
    )
    (net (code "9") (name "I2C_SCL") (class "Default")
      (node (ref "IC5") (pin "29") (pinfunction "PB10/SPI2_SCK/I2S_SCK/I2C2_SCL/USART3_TX_29") (pintype "bidirectional"))
      (node (ref "IC8") (pin "24") (pinfunction "SCLK_24") (pintype "bidirectional"))
      (node (ref "R40") (pin "1") (pinfunction "1_1") (pintype "passive"))
    )
    (net (code "10") (name "I2C_SDA") (class "Default")
      (node (ref "IC5") (pin "30") (pinfunction "PB11/I2C2_SDA/USART3_RX_30") (pintype "bidirectional"))
      (node (ref "IC8") (pin "23") (pinfunction "SDIN_23") (pintype "bidirectional"))
      (node (ref "R41") (pin "1") (pinfunction "1_1") (pintype "passive"))
    )
    (net (code "11") (name "I2S_LRCK") (class "Default")
      (node (ref "IC5") (pin "33") (pinfunction "PB12/SPI2_NSS/I2S2_WS/I2C2_SMBA/USART3_CK/TIM1_BKIN_33") (pintype "bidirectional"))
      (node (ref "IC8") (pin "5") (pinfunction "DACLRC_5") (pintype "bidirectional"))
      (node (ref "IC8") (pin "7") (pinfunction "ADCLRC_7") (pintype "bidirectional"))
    )
    (net (code "12") (name "I2S_SCK") (class "Default")
      (node (ref "IC5") (pin "34") (pinfunction "PB13/SPI2_SCK/I2S2_SCK/USART3_CTS/TIM1_CH1N_34") (pintype "bidirectional"))
      (node (ref "IC8") (pin "3") (pinfunction "BCLK_3") (pintype "bidirectional"))
    )
    (net (code "13") (name "I2S_SIN") (class "Default")
      (node (ref "IC5") (pin "35") (pinfunction "PB14/SPI2_MISO/USART3_RTS/TIM1_CH2N_35") (pintype "bidirectional"))
      (node (ref "IC8") (pin "6") (pinfunction "ADCDAT_6") (pintype "bidirectional"))
    )
    (net (code "14") (name "I2S_SOUT") (class "Default")
      (node (ref "IC5") (pin "36") (pinfunction "PB15/SPI2_MOSI/I2S2_SD/TIM1_CH3N_36") (pintype "bidirectional"))
      (node (ref "IC8") (pin "4") (pinfunction "DACDAT_4") (pintype "bidirectional"))
    )
    (net (code "15") (name "JTCK") (class "Default")
      (node (ref "IC5") (pin "49") (pinfunction "PA14/JTCK-SWCLK_49") (pintype "bidirectional"))
      (node (ref "JP2") (pin "4") (pinfunction "4_4") (pintype "passive"))
    )
    (net (code "16") (name "JTDI") (class "Default")
      (node (ref "IC5") (pin "50") (pinfunction "PA15/JTDI/SPI3_NSS/I2S3_WS_50") (pintype "bidirectional"))
      (node (ref "JP2") (pin "8") (pinfunction "8_8") (pintype "passive"))
    )
    (net (code "17") (name "JTDO") (class "Default")
      (node (ref "IC5") (pin "55") (pinfunction "PB3/JTDO/SPI3_SCK/I2S3_SCK_55") (pintype "bidirectional"))
      (node (ref "JP2") (pin "6") (pinfunction "6_6") (pintype "passive"))
    )
    (net (code "18") (name "JTMS") (class "Default")
      (node (ref "IC5") (pin "46") (pinfunction "PA13/JTMS-SWDAT_46") (pintype "bidirectional"))
      (node (ref "JP2") (pin "2") (pinfunction "2_2") (pintype "passive"))
    )
    (net (code "19") (name "LED_DATA") (class "Default")
      (node (ref "IC1") (pin "14") (pinfunction "SER_14") (pintype "input"))
      (node (ref "IC5") (pin "57") (pinfunction "PB5/I2C1_SMBA/SPI1_MOSI/SPI3_MOSI/I2S3_SD_57") (pintype "bidirectional"))
    )
    (net (code "20") (name "LED_EN") (class "Default")
      (node (ref "IC1") (pin "12") (pinfunction "RCK_12") (pintype "input"))
      (node (ref "IC5") (pin "24") (pinfunction "PC4/ADC14_24") (pintype "bidirectional"))
    )
    (net (code "21") (name "LED_REC") (class "Default")
      (node (ref "IC5") (pin "62") (pinfunction "PB9/SPI2_NSS/I2S2_WS/I2C1_SDA/TIM4_CH4_62") (pintype "bidirectional"))
      (node (ref "R1") (pin "1") (pinfunction "1_1") (pintype "passive"))
      (node (ref "R2") (pin "1") (pinfunction "1_1") (pintype "passive"))
    )
    (net (code "22") (name "LED_SCK") (class "Default")
      (node (ref "IC1") (pin "11") (pinfunction "SCK_11") (pintype "input"))
      (node (ref "IC5") (pin "25") (pinfunction "PC5/ADC15_25") (pintype "bidirectional"))
    )
    (net (code "23") (name "LIN") (class "Default")
      (node (ref "C37") (pin "+") (pinfunction "+_+") (pintype "passive"))
      (node (ref "IC8") (pin "20") (pinfunction "LLINEIN_20") (pintype "bidirectional"))
    )
    (net (code "24") (name "LOUT") (class "Default")
      (node (ref "C33") (pin "+") (pinfunction "+_+") (pintype "passive"))
      (node (ref "IC8") (pin "12") (pinfunction "LOUT_12") (pintype "bidirectional"))
    )
    (net (code "25") (name "Net-(C33-Pad-)") (class "Default")
      (node (ref "C33") (pin "-") (pinfunction "-_-") (pintype "passive"))
      (node (ref "R51") (pin "2") (pinfunction "2_2") (pintype "passive"))
      (node (ref "R59") (pin "2") (pinfunction "2_2") (pintype "passive"))
    )
    (net (code "26") (name "Net-(C36-Pad-)") (class "Default")
      (node (ref "C36") (pin "-") (pinfunction "-_-") (pintype "passive"))
      (node (ref "C43") (pin "1") (pinfunction "1_1") (pintype "passive"))
      (node (ref "R53") (pin "1") (pinfunction "1_1") (pintype "passive"))
      (node (ref "R54") (pin "2") (pinfunction "2_2") (pintype "passive"))
    )
    (net (code "27") (name "Net-(C37-Pad-)") (class "Default")
      (node (ref "C37") (pin "-") (pinfunction "-_-") (pintype "passive"))
      (node (ref "C44") (pin "1") (pinfunction "1_1") (pintype "passive"))
      (node (ref "R55") (pin "1") (pinfunction "1_1") (pintype "passive"))
      (node (ref "R56") (pin "2") (pinfunction "2_2") (pintype "passive"))
    )
    (net (code "28") (name "Net-(C41-Pad-)") (class "Default")
      (node (ref "C41") (pin "-") (pinfunction "-_-") (pintype "passive"))
      (node (ref "R50") (pin "2") (pinfunction "2_2") (pintype "passive"))
      (node (ref "R52") (pin "2") (pinfunction "2_2") (pintype "passive"))
    )
    (net (code "29") (name "Net-(D1-PadA)") (class "Default")
      (node (ref "D1") (pin "A") (pinfunction "A_A") (pintype "passive"))
      (node (ref "JP3") (pin "1") (pinfunction "1_1") (pintype "passive"))
      (node (ref "JP3") (pin "2") (pinfunction "2_2") (pintype "passive"))
    )
    (net (code "30") (name "Net-(D2-PadC)") (class "Default")
      (node (ref "D2") (pin "C") (pinfunction "C_C") (pintype "passive"))
      (node (ref "JP3") (pin "10") (pinfunction "10_10") (pintype "passive"))
      (node (ref "JP3") (pin "9") (pinfunction "9_9") (pintype "passive"))
    )
    (net (code "31") (name "Net-(IC1A-QA)") (class "Default")
      (node (ref "IC1") (pin "15") (pinfunction "QA_15") (pintype "tri_state"))
      (node (ref "R10") (pin "2") (pinfunction "2_2") (pintype "passive"))
    )
    (net (code "32") (name "Net-(IC1A-QB)") (class "Default")
      (node (ref "IC1") (pin "1") (pinfunction "QB_1") (pintype "tri_state"))
      (node (ref "R9") (pin "2") (pinfunction "2_2") (pintype "passive"))
    )
    (net (code "33") (name "Net-(IC1A-QC)") (class "Default")
      (node (ref "IC1") (pin "2") (pinfunction "QC_2") (pintype "tri_state"))
      (node (ref "R8") (pin "2") (pinfunction "2_2") (pintype "passive"))
    )
    (net (code "34") (name "Net-(IC1A-QD)") (class "Default")
      (node (ref "IC1") (pin "3") (pinfunction "QD_3") (pintype "tri_state"))
      (node (ref "R7") (pin "2") (pinfunction "2_2") (pintype "passive"))
    )
    (net (code "35") (name "Net-(IC1A-QE)") (class "Default")
      (node (ref "IC1") (pin "4") (pinfunction "QE_4") (pintype "tri_state"))
      (node (ref "R6") (pin "2") (pinfunction "2_2") (pintype "passive"))
    )
    (net (code "36") (name "Net-(IC1A-QF)") (class "Default")
      (node (ref "IC1") (pin "5") (pinfunction "QF_5") (pintype "tri_state"))
      (node (ref "R5") (pin "2") (pinfunction "2_2") (pintype "passive"))
    )
    (net (code "37") (name "Net-(IC1A-QG)") (class "Default")
      (node (ref "IC1") (pin "6") (pinfunction "QG_6") (pintype "tri_state"))
      (node (ref "R3") (pin "2") (pinfunction "2_2") (pintype "passive"))
    )
    (net (code "38") (name "Net-(IC1A-QH)") (class "Default")
      (node (ref "IC1") (pin "7") (pinfunction "QH_7") (pintype "tri_state"))
      (node (ref "R4") (pin "2") (pinfunction "2_2") (pintype "passive"))
    )
    (net (code "39") (name "Net-(IC2-VIN)") (class "Default")
      (node (ref "C2") (pin "+") (pinfunction "+_+") (pintype "passive"))
      (node (ref "IC2") (pin "2") (pinfunction "VIN_2") (pintype "input"))
      (node (ref "R11") (pin "2") (pinfunction "2_2") (pintype "passive"))
    )
    (net (code "40") (name "Net-(IC3A--IN)") (class "Default")
      (node (ref "C22") (pin "1") (pinfunction "1_1") (pintype "passive"))
      (node (ref "IC3") (pin "2") (pinfunction "-IN_2") (pintype "input"))
      (node (ref "R31") (pin "2") (pinfunction "2_2") (pintype "passive"))
      (node (ref "R32") (pin "1") (pinfunction "1_1") (pintype "passive"))
      (node (ref "R33") (pin "1") (pinfunction "1_1") (pintype "passive"))
    )
    (net (code "41") (name "Net-(IC3B--IN)") (class "Default")
      (node (ref "C9") (pin "1") (pinfunction "1_1") (pintype "passive"))
      (node (ref "IC3") (pin "6") (pinfunction "-IN_6") (pintype "input"))
      (node (ref "R27") (pin "2") (pinfunction "2_2") (pintype "passive"))
      (node (ref "R28") (pin "1") (pinfunction "1_1") (pintype "passive"))
      (node (ref "R29") (pin "1") (pinfunction "1_1") (pintype "passive"))
    )
    (net (code "42") (name "Net-(IC4A--IN)") (class "Default")
      (node (ref "C20") (pin "1") (pinfunction "1_1") (pintype "passive"))
      (node (ref "IC4") (pin "2") (pinfunction "-IN_2") (pintype "input"))
      (node (ref "R34") (pin "2") (pinfunction "2_2") (pintype "passive"))
      (node (ref "R36") (pin "1") (pinfunction "1_1") (pintype "passive"))
      (node (ref "R38") (pin "1") (pinfunction "1_1") (pintype "passive"))
    )
    (net (code "43") (name "Net-(IC4B--IN)") (class "Default")
      (node (ref "C21") (pin "1") (pinfunction "1_1") (pintype "passive"))
      (node (ref "IC4") (pin "6") (pinfunction "-IN_6") (pintype "input"))
      (node (ref "R35") (pin "2") (pinfunction "2_2") (pintype "passive"))
      (node (ref "R37") (pin "1") (pinfunction "1_1") (pintype "passive"))
      (node (ref "R39") (pin "1") (pinfunction "1_1") (pintype "passive"))
    )
    (net (code "44") (name "Net-(IC4C--IN)") (class "Default")
      (node (ref "C11") (pin "1") (pinfunction "1_1") (pintype "passive"))
      (node (ref "IC4") (pin "9") (pinfunction "-IN_9") (pintype "input"))
      (node (ref "R23") (pin "1") (pinfunction "1_1") (pintype "passive"))
      (node (ref "R24") (pin "1") (pinfunction "1_1") (pintype "passive"))
      (node (ref "R26") (pin "2") (pinfunction "2_2") (pintype "passive"))
    )
    (net (code "45") (name "Net-(IC4D--IN)") (class "Default")
      (node (ref "C10") (pin "1") (pinfunction "1_1") (pintype "passive"))
      (node (ref "IC4") (pin "13") (pinfunction "-IN_13") (pintype "input"))
      (node (ref "R21") (pin "1") (pinfunction "1_1") (pintype "passive"))
      (node (ref "R22") (pin "1") (pinfunction "1_1") (pintype "passive"))
      (node (ref "R25") (pin "2") (pinfunction "2_2") (pintype "passive"))
    )
    (net (code "46") (name "Net-(IC5-PD0{slash}OSC_IN)") (class "Default")
      (node (ref "C7") (pin "2") (pinfunction "2_2") (pintype "passive"))
      (node (ref "IC5") (pin "5") (pinfunction "PD0/OSC_IN_5") (pintype "bidirectional"))
      (node (ref "Q3") (pin "2") (pinfunction "2_2") (pintype "passive"))
    )
    (net (code "47") (name "Net-(IC5-PD1{slash}OSC_OUT)") (class "Default")
      (node (ref "C6") (pin "2") (pinfunction "2_2") (pintype "passive"))
      (node (ref "IC5") (pin "6") (pinfunction "PD1/OSC_OUT_6") (pintype "bidirectional"))
      (node (ref "Q3") (pin "1") (pinfunction "1_1") (pintype "passive"))
    )
    (net (code "48") (name "Net-(IC5-VCAP_1)") (class "Default")
      (node (ref "C24") (pin "1") (pinfunction "1_1") (pintype "passive"))
      (node (ref "IC5") (pin "31") (pinfunction "VCAP_1_31") (pintype "power_in"))
    )
    (net (code "49") (name "Net-(IC5-VCAP_2)") (class "Default")
      (node (ref "C19") (pin "1") (pinfunction "1_1") (pintype "passive"))
      (node (ref "IC5") (pin "47") (pinfunction "VCAP_2_47") (pintype "power_in"))
    )
    (net (code "50") (name "Net-(IC8-VMID)") (class "Default")
      (node (ref "C34") (pin "1") (pinfunction "1_1") (pintype "passive"))
      (node (ref "C35") (pin "+") (pinfunction "+_+") (pintype "passive"))
      (node (ref "IC8") (pin "16") (pinfunction "VMID_16") (pintype "bidirectional"))
    )
    (net (code "51") (name "Net-(IC8-XTI{slash}MCLK)") (class "Default")
      (node (ref "C48") (pin "2") (pinfunction "2_2") (pintype "passive"))
      (node (ref "IC8") (pin "25") (pinfunction "XTI/MCLK_25") (pintype "bidirectional"))
      (node (ref "Q4") (pin "2") (pinfunction "2_2") (pintype "passive"))
    )
    (net (code "52") (name "Net-(IC8-XTO)") (class "Default")
      (node (ref "C47") (pin "2") (pinfunction "2_2") (pintype "passive"))
      (node (ref "IC8") (pin "26") (pinfunction "XTO_26") (pintype "bidirectional"))
      (node (ref "Q4") (pin "1") (pinfunction "1_1") (pintype "passive"))
    )
    (net (code "53") (name "Net-(IC9A--IN)") (class "Default")
      (node (ref "IC9") (pin "2") (pinfunction "-IN_2") (pintype "input"))
      (node (ref "R46") (pin "2") (pinfunction "2_2") (pintype "passive"))
      (node (ref "R57") (pin "1") (pinfunction "1_1") (pintype "passive"))
    )
    (net (code "54") (name "Net-(IC9A-OUT)") (class "Default")
      (node (ref "IC9") (pin "1") (pinfunction "OUT_1") (pintype "output"))
      (node (ref "R42") (pin "2") (pinfunction "S_2") (pintype "passive"))
      (node (ref "R42") (pin "3") (pinfunction "E_3") (pintype "passive"))
      (node (ref "R55") (pin "2") (pinfunction "2_2") (pintype "passive"))
    )
    (net (code "55") (name "Net-(IC9B--IN)") (class "Default")
      (node (ref "IC9") (pin "6") (pinfunction "-IN_6") (pintype "input"))
      (node (ref "R47") (pin "2") (pinfunction "2_2") (pintype "passive"))
      (node (ref "R58") (pin "1") (pinfunction "1_1") (pintype "passive"))
    )
    (net (code "56") (name "Net-(IC9B-OUT)") (class "Default")
      (node (ref "IC9") (pin "7") (pinfunction "OUT_7") (pintype "output"))
      (node (ref "R42") (pin "2P") (pinfunction "S_2P") (pintype "passive"))
      (node (ref "R42") (pin "3P") (pinfunction "E_3P") (pintype "passive"))
      (node (ref "R53") (pin "2") (pinfunction "2_2") (pintype "passive"))
    )
    (net (code "57") (name "Net-(IC10A--IN)") (class "Default")
      (node (ref "C40") (pin "1") (pinfunction "1_1") (pintype "passive"))
      (node (ref "IC10") (pin "2") (pinfunction "-IN_2") (pintype "input"))
      (node (ref "R49") (pin "2") (pinfunction "2_2") (pintype "passive"))
      (node (ref "R51") (pin "1") (pinfunction "1_1") (pintype "passive"))
    )
    (net (code "58") (name "Net-(IC10A-OUT)") (class "Default")
      (node (ref "C40") (pin "2") (pinfunction "2_2") (pintype "passive"))
      (node (ref "IC10") (pin "1") (pinfunction "OUT_1") (pintype "output"))
      (node (ref "R49") (pin "1") (pinfunction "1_1") (pintype "passive"))
      (node (ref "R61") (pin "2") (pinfunction "2_2") (pintype "passive"))
    )
    (net (code "59") (name "Net-(IC10B--IN)") (class "Default")
      (node (ref "C42") (pin "1") (pinfunction "1_1") (pintype "passive"))
      (node (ref "IC10") (pin "6") (pinfunction "-IN_6") (pintype "input"))
      (node (ref "R48") (pin "2") (pinfunction "2_2") (pintype "passive"))
      (node (ref "R52") (pin "1") (pinfunction "1_1") (pintype "passive"))
    )
    (net (code "60") (name "Net-(IC10B-OUT)") (class "Default")
      (node (ref "C42") (pin "2") (pinfunction "2_2") (pintype "passive"))
      (node (ref "IC10") (pin "7") (pinfunction "OUT_7") (pintype "output"))
      (node (ref "R48") (pin "1") (pinfunction "1_1") (pintype "passive"))
      (node (ref "R62") (pin "2") (pinfunction "2_2") (pintype "passive"))
    )
    (net (code "61") (name "Net-(J1-3)") (class "Default")
      (node (ref "J1") (pin "P3") (pinfunction "3_P3") (pintype "passive"))
      (node (ref "R12") (pin "1") (pinfunction "1_1") (pintype "passive"))
    )
    (net (code "62") (name "Net-(J2-3)") (class "Default")
      (node (ref "J2") (pin "P3") (pinfunction "3_P3") (pintype "passive"))
      (node (ref "R15") (pin "1") (pinfunction "1_1") (pintype "passive"))
    )
    (net (code "63") (name "Net-(J3-3)") (class "Default")
      (node (ref "J3") (pin "P3") (pinfunction "3_P3") (pintype "passive"))
      (node (ref "R29") (pin "2") (pinfunction "2_2") (pintype "passive"))
    )
    (net (code "64") (name "Net-(J4-3)") (class "Default")
      (node (ref "J4") (pin "P3") (pinfunction "3_P3") (pintype "passive"))
      (node (ref "R21") (pin "2") (pinfunction "2_2") (pintype "passive"))
    )
    (net (code "65") (name "Net-(J5-3)") (class "Default")
      (node (ref "J5") (pin "P3") (pinfunction "3_P3") (pintype "passive"))
      (node (ref "R38") (pin "2") (pinfunction "2_2") (pintype "passive"))
    )
    (net (code "66") (name "Net-(J6-3)") (class "Default")
      (node (ref "J6") (pin "P3") (pinfunction "3_P3") (pintype "passive"))
      (node (ref "R39") (pin "2") (pinfunction "2_2") (pintype "passive"))
    )
    (net (code "67") (name "Net-(J7-3)") (class "Default")
      (node (ref "J7") (pin "P3") (pinfunction "3_P3") (pintype "passive"))
      (node (ref "J8") (pin "P2") (pinfunction "2_P2") (pintype "passive"))
      (node (ref "R57") (pin "2") (pinfunction "2_2") (pintype "passive"))
    )
    (net (code "68") (name "Net-(J8-3)") (class "Default")
      (node (ref "J8") (pin "P3") (pinfunction "3_P3") (pintype "passive"))
      (node (ref "R58") (pin "2") (pinfunction "2_2") (pintype "passive"))
    )
    (net (code "69") (name "Net-(J9-3)") (class "Default")
      (node (ref "J9") (pin "P3") (pinfunction "3_P3") (pintype "passive"))
      (node (ref "R32") (pin "2") (pinfunction "2_2") (pintype "passive"))
    )
    (net (code "70") (name "Net-(J10-3)") (class "Default")
      (node (ref "J10") (pin "P3") (pinfunction "3_P3") (pintype "passive"))
      (node (ref "R24") (pin "2") (pinfunction "2_2") (pintype "passive"))
    )
    (net (code "71") (name "Net-(J11-3)") (class "Default")
      (node (ref "J11") (pin "P3") (pinfunction "3_P3") (pintype "passive"))
      (node (ref "R61") (pin "1") (pinfunction "1_1") (pintype "passive"))
    )
    (net (code "72") (name "Net-(J12-3)") (class "Default")
      (node (ref "J12") (pin "P3") (pinfunction "3_P3") (pintype "passive"))
      (node (ref "R62") (pin "1") (pinfunction "1_1") (pintype "passive"))
    )
    (net (code "73") (name "Net-(LED1-GRN)") (class "Default")
      (node (ref "LED1") (pin "3") (pinfunction "GRN_3") (pintype "bidirectional"))
      (node (ref "R4") (pin "1") (pinfunction "1_1") (pintype "passive"))
    )
    (net (code "74") (name "Net-(LED1-RED)") (class "Default")
      (node (ref "LED1") (pin "1") (pinfunction "RED_1") (pintype "bidirectional"))
      (node (ref "R3") (pin "1") (pinfunction "1_1") (pintype "passive"))
    )
    (net (code "75") (name "Net-(LED2-GRN)") (class "Default")
      (node (ref "LED2") (pin "3") (pinfunction "GRN_3") (pintype "bidirectional"))
      (node (ref "R5") (pin "1") (pinfunction "1_1") (pintype "passive"))
    )
    (net (code "76") (name "Net-(LED2-RED)") (class "Default")
      (node (ref "LED2") (pin "1") (pinfunction "RED_1") (pintype "bidirectional"))
      (node (ref "R6") (pin "1") (pinfunction "1_1") (pintype "passive"))
    )
    (net (code "77") (name "Net-(LED3-GRN)") (class "Default")
      (node (ref "LED3") (pin "3") (pinfunction "GRN_3") (pintype "bidirectional"))
      (node (ref "R7") (pin "1") (pinfunction "1_1") (pintype "passive"))
    )
    (net (code "78") (name "Net-(LED3-RED)") (class "Default")
      (node (ref "LED3") (pin "1") (pinfunction "RED_1") (pintype "bidirectional"))
      (node (ref "R8") (pin "1") (pinfunction "1_1") (pintype "passive"))
    )
    (net (code "79") (name "Net-(LED4-GRN)") (class "Default")
      (node (ref "LED4") (pin "3") (pinfunction "GRN_3") (pintype "bidirectional"))
      (node (ref "R9") (pin "1") (pinfunction "1_1") (pintype "passive"))
    )
    (net (code "80") (name "Net-(LED4-RED)") (class "Default")
      (node (ref "LED4") (pin "1") (pinfunction "RED_1") (pintype "bidirectional"))
      (node (ref "R10") (pin "1") (pinfunction "1_1") (pintype "passive"))
    )
    (net (code "81") (name "Net-(Q1-PadB)") (class "Default")
      (node (ref "Q1") (pin "B") (pinfunction "B_B") (pintype "passive"))
      (node (ref "R12") (pin "2") (pinfunction "2_2") (pintype "passive"))
    )
    (net (code "82") (name "Net-(Q2-PadB)") (class "Default")
      (node (ref "Q2") (pin "B") (pinfunction "B_B") (pintype "passive"))
      (node (ref "R15") (pin "2") (pinfunction "2_2") (pintype "passive"))
    )
    (net (code "83") (name "Net-(R1-Pad2)") (class "Default")
      (node (ref "R1") (pin "2") (pinfunction "2_2") (pintype "passive"))
      (node (ref "R2") (pin "2") (pinfunction "2_2") (pintype "passive"))
      (node (ref "SW1") (pin "L1") (pinfunction "L1_L1") (pintype "passive"))
    )
    (net (code "84") (name "Net-(R18-S)") (class "Default")
      (node (ref "R18") (pin "P$2") (pinfunction "S_P$2") (pintype "passive"))
      (node (ref "R28") (pin "2") (pinfunction "2_2") (pintype "passive"))
    )
    (net (code "85") (name "Net-(R42A-A)") (class "Default")
      (node (ref "R42") (pin "1P") (pinfunction "A_1P") (pintype "passive"))
      (node (ref "R47") (pin "1") (pinfunction "1_1") (pintype "passive"))
    )
    (net (code "86") (name "Net-(R42B-A)") (class "Default")
      (node (ref "R42") (pin "1") (pinfunction "A_1") (pintype "passive"))
      (node (ref "R46") (pin "1") (pinfunction "1_1") (pintype "passive"))
    )
    (net (code "87") (name "Net-(R43-S)") (class "Default")
      (node (ref "R33") (pin "2") (pinfunction "2_2") (pintype "passive"))
      (node (ref "R43") (pin "P$2") (pinfunction "S_P$2") (pintype "passive"))
    )
    (net (code "88") (name "PITCH_POT") (class "Default")
      (node (ref "IC5") (pin "9") (pinfunction "PC1/ADC11_9") (pintype "bidirectional"))
      (node (ref "R20") (pin "P$2") (pinfunction "S_P$2") (pintype "passive"))
    )
    (net (code "89") (name "PLAY") (class "Default")
      (node (ref "IC5") (pin "58") (pinfunction "PB6/I2C1_SCL/TIM4_CH1/USART1_TX_58") (pintype "bidirectional"))
      (node (ref "Q2") (pin "C") (pinfunction "C_C") (pintype "passive"))
      (node (ref "R16") (pin "1") (pinfunction "1_1") (pintype "passive"))
    )
    (net (code "90") (name "POSITION_POT_CV") (class "Default")
      (node (ref "C9") (pin "2") (pinfunction "2_2") (pintype "passive"))
      (node (ref "IC3") (pin "7") (pinfunction "OUT_7") (pintype "output"))
      (node (ref "IC5") (pin "16") (pinfunction "PA2/USART2_TX/ADC2/TIM2_CH3_16") (pintype "bidirectional"))
      (node (ref "R27") (pin "1") (pinfunction "1_1") (pintype "passive"))
    )
    (net (code "91") (name "REC") (class "Default")
      (node (ref "IC5") (pin "59") (pinfunction "PB7/I2C1_SDA/TIM4_CH2/USART1_RX_59") (pintype "bidirectional"))
      (node (ref "Q1") (pin "C") (pinfunction "C_C") (pintype "passive"))
      (node (ref "R14") (pin "1") (pinfunction "1_1") (pintype "passive"))
    )
    (net (code "92") (name "RESET") (class "Default")
      (node (ref "IC5") (pin "7") (pinfunction "NRST_7") (pintype "bidirectional"))
      (node (ref "JP2") (pin "10") (pinfunction "10_10") (pintype "passive"))
      (node (ref "R17") (pin "1") (pinfunction "1_1") (pintype "passive"))
      (node (ref "SW5") (pin "B") (pinfunction "S_B") (pintype "passive"))
      (node (ref "SW5") (pin "B'") (pinfunction "S1_B'") (pintype "passive"))
    )
    (net (code "93") (name "RIN") (class "Default")
      (node (ref "C36") (pin "+") (pinfunction "+_+") (pintype "passive"))
      (node (ref "IC8") (pin "19") (pinfunction "RLINEIN_19") (pintype "bidirectional"))
    )
    (net (code "94") (name "ROUT") (class "Default")
      (node (ref "C41") (pin "+") (pinfunction "+_+") (pintype "passive"))
      (node (ref "IC8") (pin "13") (pinfunction "ROUT_13") (pintype "bidirectional"))
    )
    (net (code "95") (name "RX") (class "Default")
      (node (ref "IC5") (pin "43") (pinfunction "PA10/USART1_RX/TIM1_CH3_43") (pintype "bidirectional"))
      (node (ref "JP1") (pin "4") (pinfunction "4_4") (pintype "passive"))
    )
    (net (code "96") (name "SIZE_CV") (class "Default")
      (node (ref "C10") (pin "2") (pinfunction "2_2") (pintype "passive"))
      (node (ref "IC4") (pin "14") (pinfunction "OUT_14") (pintype "output"))
      (node (ref "IC5") (pin "15") (pinfunction "PA1/USART2_RTS/UART4_RX/ADC1/TIM2_CH2_15") (pintype "bidirectional"))
      (node (ref "R25") (pin "1") (pinfunction "1_1") (pintype "passive"))
    )
    (net (code "97") (name "SIZE_POT") (class "Default")
      (node (ref "IC5") (pin "8") (pinfunction "PC0/ADC10_8") (pintype "bidirectional"))
      (node (ref "R19") (pin "P$2") (pinfunction "S_P$2") (pintype "passive"))
    )
    (net (code "98") (name "SW_LOAD") (class "Default")
      (node (ref "IC5") (pin "51") (pinfunction "PC10/SPI3_SCK/I2S3_SCK/UART4_TX_51") (pintype "bidirectional"))
      (node (ref "SW3") (pin "3") (pinfunction "3_3") (pintype "passive"))
      (node (ref "SW3") (pin "4") (pinfunction "4_4") (pintype "passive"))
    )
    (net (code "99") (name "SW_MODE") (class "Default")
      (node (ref "IC5") (pin "52") (pinfunction "PC11/UART4_RX/SPI3_MISO/USART3_RX_52") (pintype "bidirectional"))
      (node (ref "SW2") (pin "3") (pinfunction "3_3") (pintype "passive"))
      (node (ref "SW2") (pin "4") (pinfunction "4_4") (pintype "passive"))
    )
    (net (code "100") (name "SW_REC") (class "Default")
      (node (ref "IC5") (pin "61") (pinfunction "PB8/TIM4_CH3/I2C1_SCL_61") (pintype "bidirectional"))
      (node (ref "SW1") (pin "P2") (pinfunction "A2_P2") (pintype "passive"))
      (node (ref "SW1") (pin "P5") (pinfunction "B2_P5") (pintype "passive"))
    )
    (net (code "101") (name "TEXTURE_CV") (class "Default")
      (node (ref "C11") (pin "2") (pinfunction "2_2") (pintype "passive"))
      (node (ref "IC4") (pin "8") (pinfunction "OUT_8") (pintype "output"))
      (node (ref "IC5") (pin "14") (pinfunction "PA0-WKUP/USART2_CTS/UART4_TX/ADC0/TIM2_CH1_ETR_14") (pintype "bidirectional"))
      (node (ref "R26") (pin "1") (pinfunction "1_1") (pintype "passive"))
    )
    (net (code "102") (name "TEXTURE_POT") (class "Default")
      (node (ref "IC5") (pin "22") (pinfunction "PA6/SPI1_MISO/ADC6/TIM3_CH1_22") (pintype "bidirectional"))
      (node (ref "R44") (pin "P$2") (pinfunction "S_P$2") (pintype "passive"))
    )
    (net (code "103") (name "TX") (class "Default")
      (node (ref "IC5") (pin "42") (pinfunction "PA9/USART1_TX/TIM1_CH2_42") (pintype "bidirectional"))
      (node (ref "JP1") (pin "5") (pinfunction "5_5") (pintype "passive"))
    )
    (net (code "104") (name "VBAT") (class "Default")
      (node (ref "IC5") (pin "1") (pinfunction "VBAT_1") (pintype "power_in"))
    )
    (net (code "105") (name "VCC") (class "Default")
      (node (ref "C1") (pin "+") (pinfunction "+_+") (pintype "passive"))
      (node (ref "C38") (pin "1") (pinfunction "1_1") (pintype "passive"))
      (node (ref "C39") (pin "1") (pinfunction "1_1") (pintype "passive"))
      (node (ref "D1") (pin "C") (pinfunction "C_C") (pintype "passive"))
      (node (ref "IC10") (pin "8") (pinfunction "V+_8") (pintype "power_in"))
      (node (ref "IC7") (pin "3") (pinfunction "VIN_3") (pintype "input"))
      (node (ref "IC9") (pin "8") (pinfunction "V+_8") (pintype "power_in"))
      (node (ref "R11") (pin "1") (pinfunction "1_1") (pintype "passive"))
    )
    (net (code "106") (name "VEE") (class "Default")
      (node (ref "C13") (pin "-") (pinfunction "-_-") (pintype "passive"))
      (node (ref "C45") (pin "2") (pinfunction "2_2") (pintype "passive"))
      (node (ref "C46") (pin "2") (pinfunction "2_2") (pintype "passive"))
      (node (ref "D2") (pin "A") (pinfunction "A_A") (pintype "passive"))
      (node (ref "IC10") (pin "4") (pinfunction "V-_4") (pintype "power_in"))
      (node (ref "IC9") (pin "4") (pinfunction "V-_4") (pintype "power_in"))
      (node (ref "R30") (pin "1") (pinfunction "1_1") (pintype "passive"))
    )
    (net (code "107") (name "V_OCT") (class "Default")
      (node (ref "C20") (pin "2") (pinfunction "2_2") (pintype "passive"))
      (node (ref "IC4") (pin "1") (pinfunction "OUT_1") (pintype "output"))
      (node (ref "IC5") (pin "20") (pinfunction "PA4/SPI1_NSS/SPI3_NSS/USART2_CK/I2S3_WS/ADC4/DAC1_20") (pintype "bidirectional"))
      (node (ref "R34") (pin "1") (pinfunction "1_1") (pintype "passive"))
    )
    (net (code "108") (name "unconnected-(IC1A-QH*-Pad9)") (class "Default")
      (node (ref "IC1") (pin "9") (pinfunction "QH*_9") (pintype "tri_state"))
    )
    (net (code "109") (name "unconnected-(IC5-PA8{slash}USART1_CK{slash}TIM1_CH1{slash}MCO-Pad41)") (class "Default")
      (node (ref "IC5") (pin "41") (pinfunction "PA8/USART1_CK/TIM1_CH1/MCO_41") (pintype "bidirectional"))
    )
    (net (code "110") (name "unconnected-(IC5-PA11{slash}USART1_CTS{slash}CANRX{slash}USBDM{slash}TIM1_CH4-Pad44)") (class "Default")
      (node (ref "IC5") (pin "44") (pinfunction "PA11/USART1_CTS/CANRX/USBDM/TIM1_CH4_44") (pintype "bidirectional"))
    )
    (net (code "111") (name "unconnected-(IC5-PA12{slash}USART1_RTS{slash}CANTX{slash}USBDP{slash}TIM1_ETR-Pad45)") (class "Default")
      (node (ref "IC5") (pin "45") (pinfunction "PA12/USART1_RTS/CANTX/USBDP/TIM1_ETR_45") (pintype "bidirectional"))
    )
    (net (code "112") (name "unconnected-(IC5-PB1{slash}ADC9{slash}TIM3_CH4-Pad27)") (class "Default")
      (node (ref "IC5") (pin "27") (pinfunction "PB1/ADC9/TIM3_CH4_27") (pintype "bidirectional"))
    )
    (net (code "113") (name "unconnected-(IC5-PB4{slash}NJTRST{slash}SPI3_MISO{slash}SPI1_MISO-Pad56)") (class "Default")
      (node (ref "IC5") (pin "56") (pinfunction "PB4/NJTRST/SPI3_MISO/SPI1_MISO_56") (pintype "bidirectional"))
    )
    (net (code "114") (name "unconnected-(IC5-PC2{slash}SPI2_MISO{slash}ADC12-Pad10)") (class "Default")
      (node (ref "IC5") (pin "10") (pinfunction "PC2/SPI2_MISO/ADC12_10") (pintype "bidirectional"))
    )
    (net (code "115") (name "unconnected-(IC5-PC3{slash}SPI2_MOSI{slash}I2S2_SD{slash}ADC13-Pad11)") (class "Default")
      (node (ref "IC5") (pin "11") (pinfunction "PC3/SPI2_MOSI/I2S2_SD/ADC13_11") (pintype "bidirectional"))
    )
    (net (code "116") (name "unconnected-(IC5-PC6{slash}I2S2_MCK-Pad37)") (class "Default")
      (node (ref "IC5") (pin "37") (pinfunction "PC6/I2S2_MCK_37") (pintype "bidirectional"))
    )
    (net (code "117") (name "unconnected-(IC5-PC7{slash}I2S3_MCK-Pad38)") (class "Default")
      (node (ref "IC5") (pin "38") (pinfunction "PC7/I2S3_MCK_38") (pintype "bidirectional"))
    )
    (net (code "118") (name "unconnected-(IC5-PC8-Pad39)") (class "Default")
      (node (ref "IC5") (pin "39") (pinfunction "PC8_39") (pintype "bidirectional"))
    )
    (net (code "119") (name "unconnected-(IC5-PC9{slash}I2S2_CKIN{slash}I2S3_CKIN-Pad40)") (class "Default")
      (node (ref "IC5") (pin "40") (pinfunction "PC9/I2S2_CKIN/I2S3_CKIN_40") (pintype "bidirectional"))
    )
    (net (code "120") (name "unconnected-(IC5-PC12{slash}UART5_TX{slash}I2S3_SD{slash}USART3_CK-Pad53)") (class "Default")
      (node (ref "IC5") (pin "53") (pinfunction "PC12/UART5_TX/I2S3_SD/USART3_CK_53") (pintype "bidirectional"))
    )
    (net (code "121") (name "unconnected-(IC5-PC13-TAMPER-RTC-Pad2)") (class "Default")
      (node (ref "IC5") (pin "2") (pinfunction "PC13-TAMPER-RTC_2") (pintype "bidirectional"))
    )
    (net (code "122") (name "unconnected-(IC5-PC14{slash}OSC32_IN-Pad3)") (class "Default")
      (node (ref "IC5") (pin "3") (pinfunction "PC14/OSC32_IN_3") (pintype "bidirectional"))
    )
    (net (code "123") (name "unconnected-(IC5-PC15{slash}OSC_OUT-Pad4)") (class "Default")
      (node (ref "IC5") (pin "4") (pinfunction "PC15/OSC_OUT_4") (pintype "bidirectional"))
    )
    (net (code "124") (name "unconnected-(IC5-PD2{slash}TIM3-ETR-Pad54)") (class "Default")
      (node (ref "IC5") (pin "54") (pinfunction "PD2/TIM3-ETR_54") (pintype "bidirectional"))
    )
    (net (code "125") (name "unconnected-(IC8-CLKOUT-Pad2)") (class "Default")
      (node (ref "IC8") (pin "2") (pinfunction "CLKOUT_2") (pintype "bidirectional"))
    )
    (net (code "126") (name "unconnected-(IC8-LHPOUT-Pad9)") (class "Default")
      (node (ref "IC8") (pin "9") (pinfunction "LHPOUT_9") (pintype "bidirectional"))
    )
    (net (code "127") (name "unconnected-(IC8-MICBIAS-Pad17)") (class "Default")
      (node (ref "IC8") (pin "17") (pinfunction "MICBIAS_17") (pintype "bidirectional"))
    )
    (net (code "128") (name "unconnected-(IC8-MICIN-Pad18)") (class "Default")
      (node (ref "IC8") (pin "18") (pinfunction "MICIN_18") (pintype "bidirectional"))
    )
    (net (code "129") (name "unconnected-(IC8-RHPOUT-Pad10)") (class "Default")
      (node (ref "IC8") (pin "10") (pinfunction "RHPOUT_10") (pintype "bidirectional"))
    )
    (net (code "130") (name "unconnected-(J3-2-PadP2)") (class "Default")
      (node (ref "J3") (pin "P2") (pinfunction "2_P2") (pintype "passive"))
    )
    (net (code "131") (name "unconnected-(J4-2-PadP2)") (class "Default")
      (node (ref "J4") (pin "P2") (pinfunction "2_P2") (pintype "passive"))
    )
    (net (code "132") (name "unconnected-(J5-2-PadP2)") (class "Default")
      (node (ref "J5") (pin "P2") (pinfunction "2_P2") (pintype "passive"))
    )
    (net (code "133") (name "unconnected-(J6-2-PadP2)") (class "Default")
      (node (ref "J6") (pin "P2") (pinfunction "2_P2") (pintype "passive"))
    )
    (net (code "134") (name "unconnected-(J7-2-PadP2)") (class "Default")
      (node (ref "J7") (pin "P2") (pinfunction "2_P2") (pintype "passive"))
    )
    (net (code "135") (name "unconnected-(J9-2-PadP2)") (class "Default")
      (node (ref "J9") (pin "P2") (pinfunction "2_P2") (pintype "passive"))
    )
    (net (code "136") (name "unconnected-(J10-2-PadP2)") (class "Default")
      (node (ref "J10") (pin "P2") (pinfunction "2_P2") (pintype "passive"))
    )
    (net (code "137") (name "unconnected-(J11-2-PadP2)") (class "Default")
      (node (ref "J11") (pin "P2") (pinfunction "2_P2") (pintype "passive"))
    )
    (net (code "138") (name "unconnected-(J12-2-PadP2)") (class "Default")
      (node (ref "J12") (pin "P2") (pinfunction "2_P2") (pintype "passive"))
    )
    (net (code "139") (name "unconnected-(JP1-Pad2)") (class "Default")
      (node (ref "JP1") (pin "2") (pinfunction "2_2") (pintype "passive"))
    )
    (net (code "140") (name "unconnected-(JP1-Pad3)") (class "Default")
      (node (ref "JP1") (pin "3") (pinfunction "3_3") (pintype "passive"))
    )
    (net (code "141") (name "unconnected-(JP1-Pad6)") (class "Default")
      (node (ref "JP1") (pin "6") (pinfunction "6_6") (pintype "passive"))
    )
    (net (code "142") (name "unconnected-(JP2-Pad7)") (class "Default")
      (node (ref "JP2") (pin "7") (pinfunction "7_7") (pintype "passive"))
    )
    (net (code "143") (name "unconnected-(SW1A-A1-PadP1)") (class "Default")
      (node (ref "SW1") (pin "P1") (pinfunction "A1_P1") (pintype "passive"))
    )
    (net (code "144") (name "unconnected-(SW1A-B1-PadP4)") (class "Default")
      (node (ref "SW1") (pin "P4") (pinfunction "B1_P4") (pintype "passive"))
    )
  )
)
